# MainBoard_ETH.net
KiCad netlist of a schematic drawn in Altium Designer
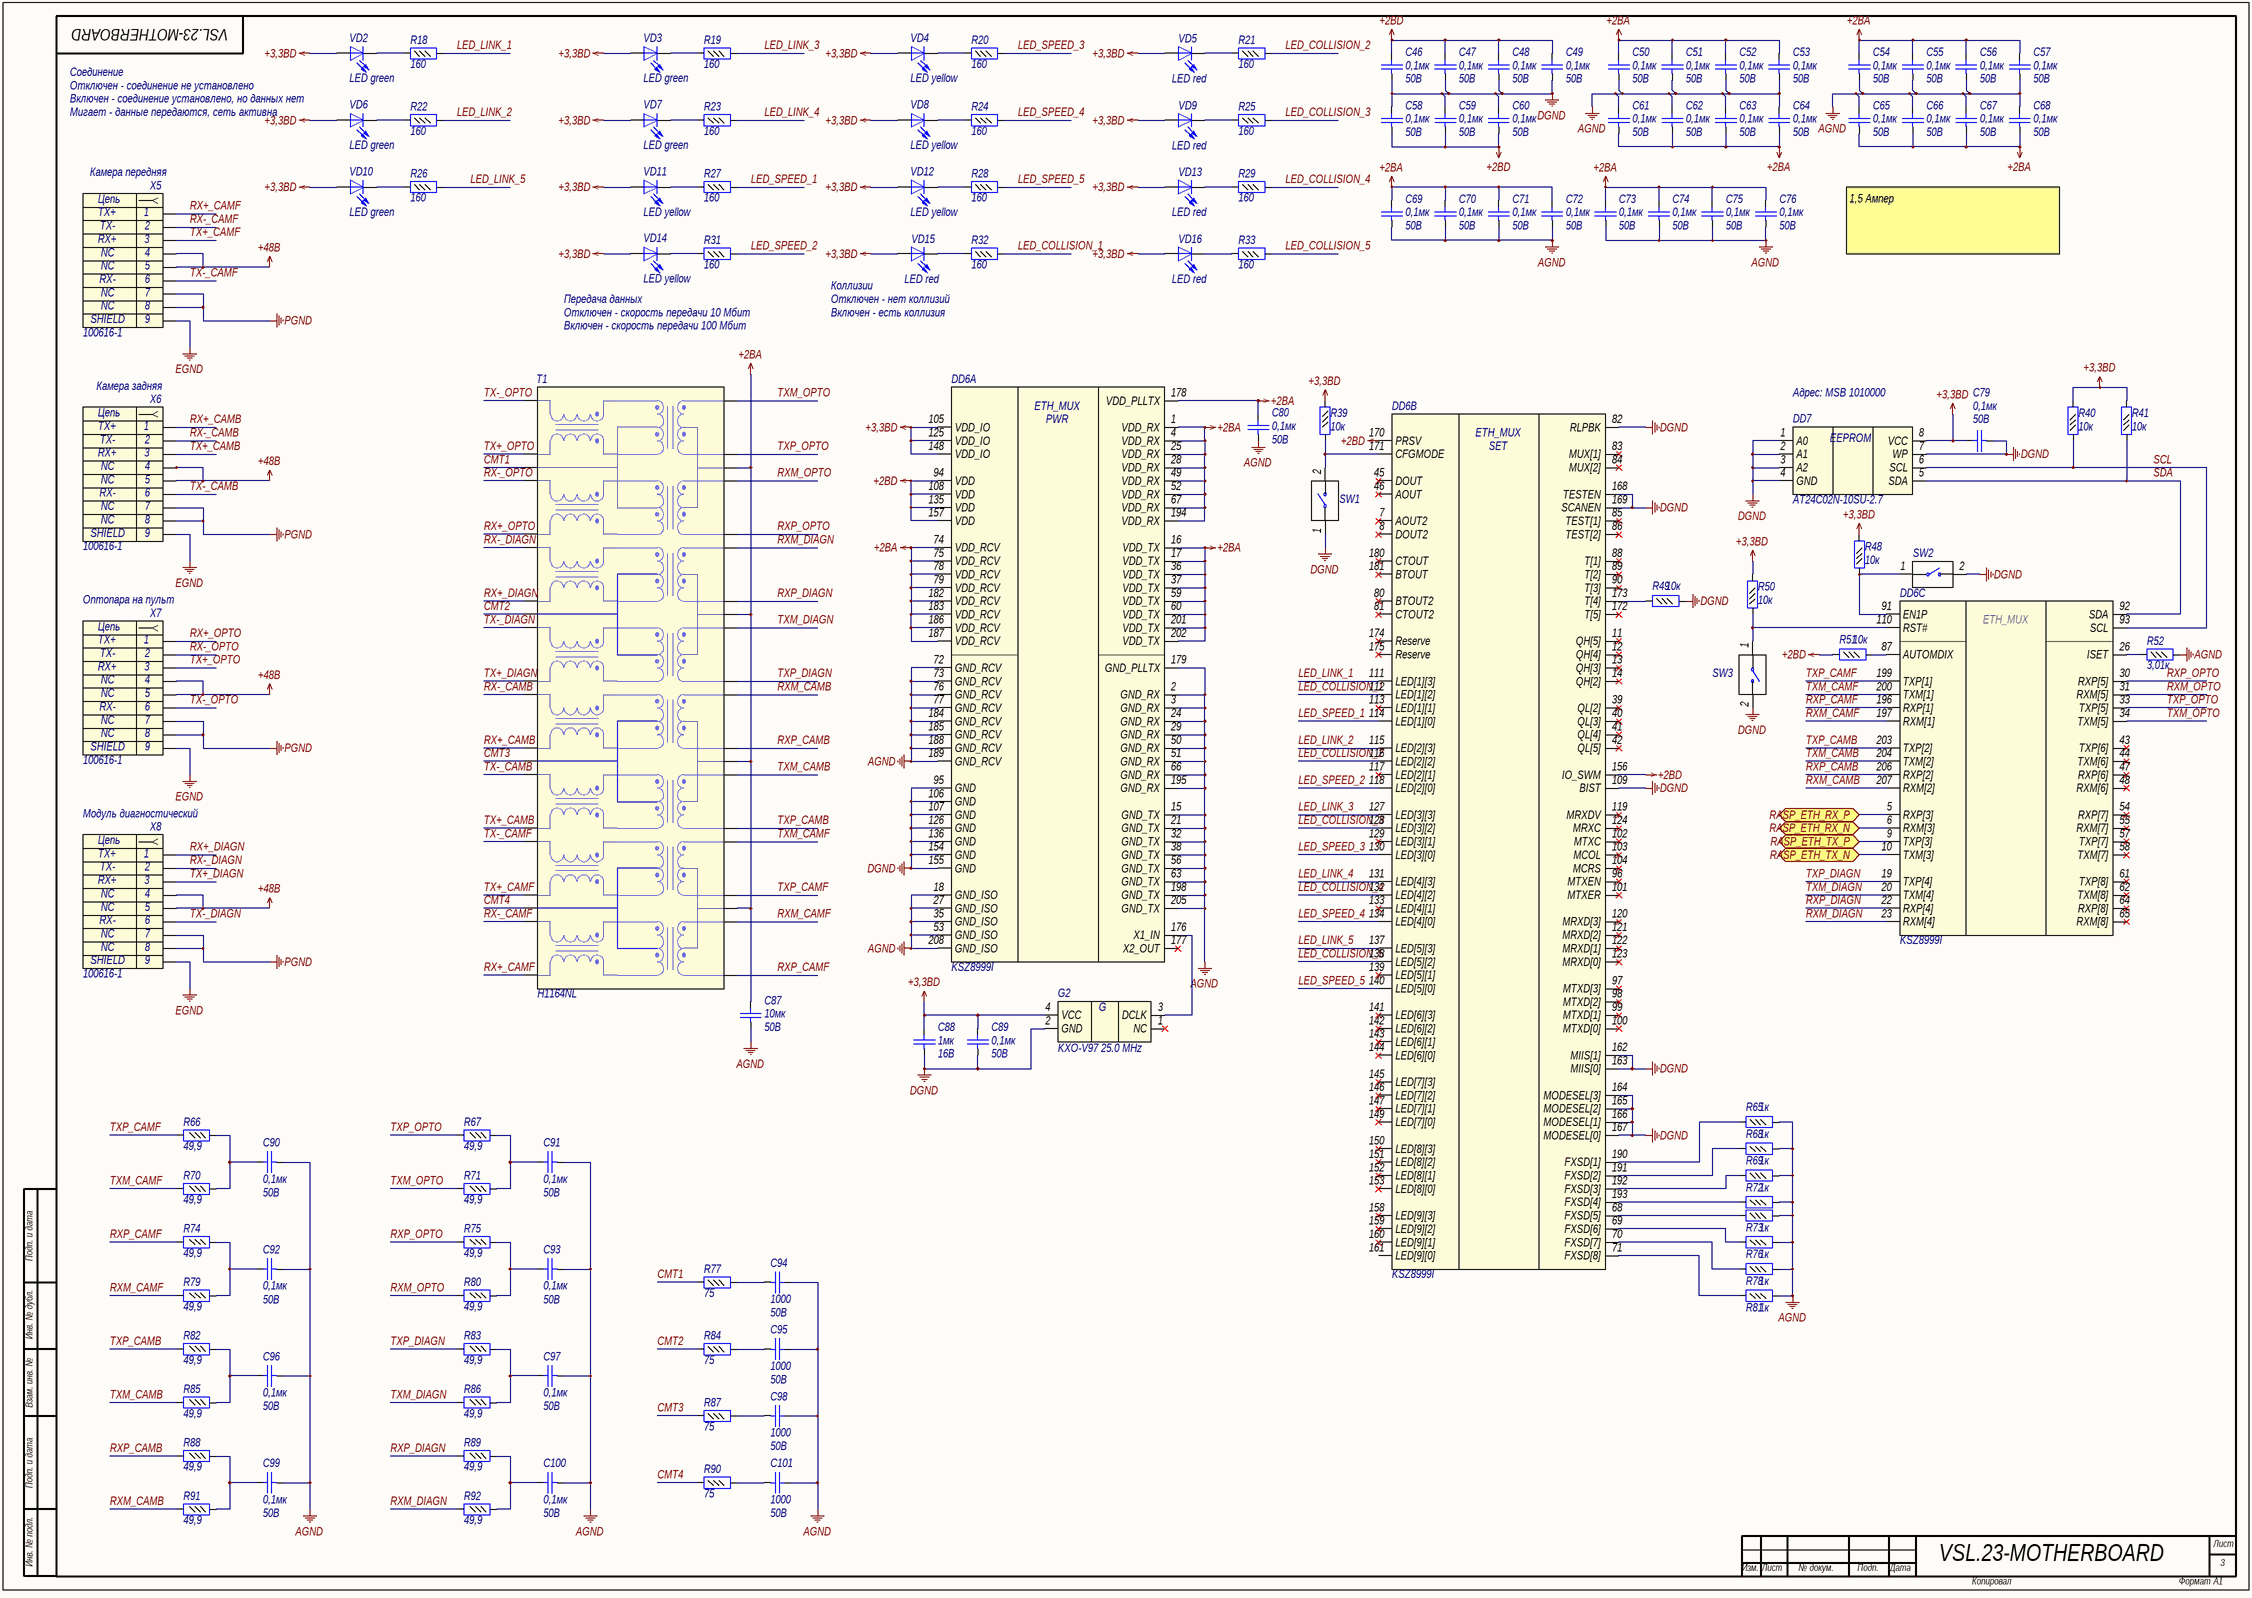
[diagram p0: MainBoard_ETH.SchDoc]

(export (version "E")
  (design (tool "Eeschema 10.0.6"))
  (components
    (comp (ref "C46")
      (value "0,1мк")
      (footprint "C0402")
      (description "Конденсатор")
      (fields
        (field (name "VOLTAGE") "50В")
        (field (name "PART NUMBER") "GRM155R71H104KE14D ")
        (field (name "Comment") "Capacitor")
      )
      (libsource (lib "MOP44") (part "Capacitor"))
    )
    (comp (ref "C47")
      (value "0,1мк")
      (footprint "C0402")
      (description "Конденсатор")
      (fields
        (field (name "VOLTAGE") "50В")
        (field (name "PART NUMBER") "GRM155R71H104KE14D ")
        (field (name "Comment") "Capacitor")
      )
      (libsource (lib "MOP44") (part "Capacitor"))
    )
    (comp (ref "C48")
      (value "0,1мк")
      (footprint "C0402")
      (description "Конденсатор")
      (fields
        (field (name "VOLTAGE") "50В")
        (field (name "PART NUMBER") "GRM155R71H104KE14D ")
        (field (name "Comment") "Capacitor")
      )
      (libsource (lib "MOP44") (part "Capacitor"))
    )
    (comp (ref "C49")
      (value "0,1мк")
      (footprint "C0402")
      (description "Конденсатор")
      (fields
        (field (name "VOLTAGE") "50В")
        (field (name "PART NUMBER") "GRM155R71H104KE14D ")
        (field (name "Comment") "Capacitor")
      )
      (libsource (lib "MOP44") (part "Capacitor"))
    )
    (comp (ref "C50")
      (value "0,1мк")
      (footprint "C0402")
      (description "Конденсатор")
      (fields
        (field (name "VOLTAGE") "50В")
        (field (name "PART NUMBER") "GRM155R71H104KE14D ")
        (field (name "Comment") "Capacitor")
      )
      (libsource (lib "MOP44") (part "Capacitor"))
    )
    (comp (ref "C51")
      (value "0,1мк")
      (footprint "C0402")
      (description "Конденсатор")
      (fields
        (field (name "VOLTAGE") "50В")
        (field (name "PART NUMBER") "GRM155R71H104KE14D ")
        (field (name "Comment") "Capacitor")
      )
      (libsource (lib "MOP44") (part "Capacitor"))
    )
    (comp (ref "C52")
      (value "0,1мк")
      (footprint "C0402")
      (description "Конденсатор")
      (fields
        (field (name "VOLTAGE") "50В")
        (field (name "PART NUMBER") "GRM155R71H104KE14D ")
        (field (name "Comment") "Capacitor")
      )
      (libsource (lib "MOP44") (part "Capacitor"))
    )
    (comp (ref "C53")
      (value "0,1мк")
      (footprint "C0402")
      (description "Конденсатор")
      (fields
        (field (name "VOLTAGE") "50В")
        (field (name "PART NUMBER") "GRM155R71H104KE14D ")
        (field (name "Comment") "Capacitor")
      )
      (libsource (lib "MOP44") (part "Capacitor"))
    )
    (comp (ref "C54")
      (value "0,1мк")
      (footprint "C0402")
      (description "Конденсатор")
      (fields
        (field (name "VOLTAGE") "50В")
        (field (name "PART NUMBER") "GRM155R71H104KE14D ")
        (field (name "Comment") "Capacitor")
      )
      (libsource (lib "MOP44") (part "Capacitor"))
    )
    (comp (ref "C55")
      (value "0,1мк")
      (footprint "C0402")
      (description "Конденсатор")
      (fields
        (field (name "VOLTAGE") "50В")
        (field (name "PART NUMBER") "GRM155R71H104KE14D ")
        (field (name "Comment") "Capacitor")
      )
      (libsource (lib "MOP44") (part "Capacitor"))
    )
    (comp (ref "C56")
      (value "0,1мк")
      (footprint "C0402")
      (description "Конденсатор")
      (fields
        (field (name "VOLTAGE") "50В")
        (field (name "PART NUMBER") "GRM155R71H104KE14D ")
        (field (name "Comment") "Capacitor")
      )
      (libsource (lib "MOP44") (part "Capacitor"))
    )
    (comp (ref "C57")
      (value "0,1мк")
      (footprint "C0402")
      (description "Конденсатор")
      (fields
        (field (name "VOLTAGE") "50В")
        (field (name "PART NUMBER") "GRM155R71H104KE14D ")
        (field (name "Comment") "Capacitor")
      )
      (libsource (lib "MOP44") (part "Capacitor"))
    )
    (comp (ref "C58")
      (value "0,1мк")
      (footprint "C0402")
      (description "Конденсатор")
      (fields
        (field (name "VOLTAGE") "50В")
        (field (name "PART NUMBER") "GRM155R71H104KE14D ")
        (field (name "Comment") "Capacitor")
      )
      (libsource (lib "MOP44") (part "Capacitor"))
    )
    (comp (ref "C59")
      (value "0,1мк")
      (footprint "C0402")
      (description "Конденсатор")
      (fields
        (field (name "VOLTAGE") "50В")
        (field (name "PART NUMBER") "GRM155R71H104KE14D ")
        (field (name "Comment") "Capacitor")
      )
      (libsource (lib "MOP44") (part "Capacitor"))
    )
    (comp (ref "C60")
      (value "0,1мк")
      (footprint "C0402")
      (description "Конденсатор")
      (fields
        (field (name "VOLTAGE") "50В")
        (field (name "PART NUMBER") "GRM155R71H104KE14D ")
        (field (name "Comment") "Capacitor")
      )
      (libsource (lib "MOP44") (part "Capacitor"))
    )
    (comp (ref "C61")
      (value "0,1мк")
      (footprint "C0402")
      (description "Конденсатор")
      (fields
        (field (name "VOLTAGE") "50В")
        (field (name "PART NUMBER") "GRM155R71H104KE14D ")
        (field (name "Comment") "Capacitor")
      )
      (libsource (lib "MOP44") (part "Capacitor"))
    )
    (comp (ref "C62")
      (value "0,1мк")
      (footprint "C0402")
      (description "Конденсатор")
      (fields
        (field (name "VOLTAGE") "50В")
        (field (name "PART NUMBER") "GRM155R71H104KE14D ")
        (field (name "Comment") "Capacitor")
      )
      (libsource (lib "MOP44") (part "Capacitor"))
    )
    (comp (ref "C63")
      (value "0,1мк")
      (footprint "C0402")
      (description "Конденсатор")
      (fields
        (field (name "VOLTAGE") "50В")
        (field (name "PART NUMBER") "GRM155R71H104KE14D ")
        (field (name "Comment") "Capacitor")
      )
      (libsource (lib "MOP44") (part "Capacitor"))
    )
    (comp (ref "C64")
      (value "0,1мк")
      (footprint "C0402")
      (description "Конденсатор")
      (fields
        (field (name "VOLTAGE") "50В")
        (field (name "PART NUMBER") "GRM155R71H104KE14D ")
        (field (name "Comment") "Capacitor")
      )
      (libsource (lib "MOP44") (part "Capacitor"))
    )
    (comp (ref "C65")
      (value "0,1мк")
      (footprint "C0402")
      (description "Конденсатор")
      (fields
        (field (name "VOLTAGE") "50В")
        (field (name "PART NUMBER") "GRM155R71H104KE14D ")
        (field (name "Comment") "Capacitor")
      )
      (libsource (lib "MOP44") (part "Capacitor"))
    )
    (comp (ref "C66")
      (value "0,1мк")
      (footprint "C0402")
      (description "Конденсатор")
      (fields
        (field (name "VOLTAGE") "50В")
        (field (name "PART NUMBER") "GRM155R71H104KE14D ")
        (field (name "Comment") "Capacitor")
      )
      (libsource (lib "MOP44") (part "Capacitor"))
    )
    (comp (ref "C67")
      (value "0,1мк")
      (footprint "C0402")
      (description "Конденсатор")
      (fields
        (field (name "VOLTAGE") "50В")
        (field (name "PART NUMBER") "GRM155R71H104KE14D ")
        (field (name "Comment") "Capacitor")
      )
      (libsource (lib "MOP44") (part "Capacitor"))
    )
    (comp (ref "C68")
      (value "0,1мк")
      (footprint "C0402")
      (description "Конденсатор")
      (fields
        (field (name "VOLTAGE") "50В")
        (field (name "PART NUMBER") "GRM155R71H104KE14D ")
        (field (name "Comment") "Capacitor")
      )
      (libsource (lib "MOP44") (part "Capacitor"))
    )
    (comp (ref "C69")
      (value "0,1мк")
      (footprint "C0402")
      (description "Конденсатор")
      (fields
        (field (name "VOLTAGE") "50В")
        (field (name "PART NUMBER") "GRM155R71H104KE14D ")
        (field (name "Comment") "Capacitor")
      )
      (libsource (lib "MOP44") (part "Capacitor"))
    )
    (comp (ref "C70")
      (value "0,1мк")
      (footprint "C0402")
      (description "Конденсатор")
      (fields
        (field (name "VOLTAGE") "50В")
        (field (name "PART NUMBER") "GRM155R71H104KE14D ")
        (field (name "Comment") "Capacitor")
      )
      (libsource (lib "MOP44") (part "Capacitor"))
    )
    (comp (ref "C71")
      (value "0,1мк")
      (footprint "C0402")
      (description "Конденсатор")
      (fields
        (field (name "VOLTAGE") "50В")
        (field (name "PART NUMBER") "GRM155R71H104KE14D ")
        (field (name "Comment") "Capacitor")
      )
      (libsource (lib "MOP44") (part "Capacitor"))
    )
    (comp (ref "C72")
      (value "0,1мк")
      (footprint "C0402")
      (description "Конденсатор")
      (fields
        (field (name "VOLTAGE") "50В")
        (field (name "PART NUMBER") "GRM155R71H104KE14D ")
        (field (name "Comment") "Capacitor")
      )
      (libsource (lib "MOP44") (part "Capacitor"))
    )
    (comp (ref "C73")
      (value "0,1мк")
      (footprint "C0402")
      (description "Конденсатор")
      (fields
        (field (name "VOLTAGE") "50В")
        (field (name "PART NUMBER") "GRM155R71H104KE14D ")
        (field (name "Comment") "Capacitor")
      )
      (libsource (lib "MOP44") (part "Capacitor"))
    )
    (comp (ref "C74")
      (value "0,1мк")
      (footprint "C0402")
      (description "Конденсатор")
      (fields
        (field (name "VOLTAGE") "50В")
        (field (name "PART NUMBER") "GRM155R71H104KE14D ")
        (field (name "Comment") "Capacitor")
      )
      (libsource (lib "MOP44") (part "Capacitor"))
    )
    (comp (ref "C75")
      (value "0,1мк")
      (footprint "C0402")
      (description "Конденсатор")
      (fields
        (field (name "VOLTAGE") "50В")
        (field (name "PART NUMBER") "GRM155R71H104KE14D ")
        (field (name "Comment") "Capacitor")
      )
      (libsource (lib "MOP44") (part "Capacitor"))
    )
    (comp (ref "C76")
      (value "0,1мк")
      (footprint "C0402")
      (description "Конденсатор")
      (fields
        (field (name "VOLTAGE") "50В")
        (field (name "PART NUMBER") "GRM155R71H104KE14D ")
        (field (name "Comment") "Capacitor")
      )
      (libsource (lib "MOP44") (part "Capacitor"))
    )
    (comp (ref "C79")
      (value "0,1мк")
      (footprint "C0402")
      (description "Конденсатор")
      (fields
        (field (name "VOLTAGE") "50В")
        (field (name "PART NUMBER") "GRM155R71H104KE14D ")
        (field (name "Comment") "Capacitor")
      )
      (libsource (lib "MOP44") (part "Capacitor"))
    )
    (comp (ref "C80")
      (value "0,1мк")
      (footprint "C0402")
      (description "Конденсатор")
      (fields
        (field (name "VOLTAGE") "50В")
        (field (name "PART NUMBER") "GRM155R71H104KE14D ")
        (field (name "Comment") "Capacitor")
      )
      (libsource (lib "MOP44") (part "Capacitor"))
    )
    (comp (ref "C87")
      (value "10мк")
      (footprint "C1210")
      (description "Конденсатор")
      (fields (field (name "VOLTAGE") "50В") (field (name "PART NUMBER") "C3225X7R1H106K250AC"))
      (libsource (lib "MOP44") (part "Capacitor"))
    )
    (comp (ref "C88")
      (value "1мк")
      (footprint "C0603")
      (description "Конденсатор")
      (fields
        (field (name "VOLTAGE") "16B")
        (field (name "PART NUMBER") "GRM188R71C105KA12D**")
        (field (name "Comment") "Capacitor")
      )
      (libsource (lib "MOP44") (part "Capacitor"))
    )
    (comp (ref "C89")
      (value "0,1мк")
      (footprint "C0402")
      (description "Конденсатор")
      (fields
        (field (name "VOLTAGE") "50В")
        (field (name "PART NUMBER") "GRM155R71H104KE14D ")
        (field (name "Comment") "Capacitor")
      )
      (libsource (lib "MOP44") (part "Capacitor"))
    )
    (comp (ref "C90")
      (value "0,1мк")
      (footprint "C0402")
      (description "Конденсатор")
      (fields
        (field (name "VOLTAGE") "50В")
        (field (name "PART NUMBER") "GRM155R71H104KE14D ")
        (field (name "Comment") "Capacitor")
      )
      (libsource (lib "MOP44") (part "Capacitor"))
    )
    (comp (ref "C91")
      (value "0,1мк")
      (footprint "C0402")
      (description "Конденсатор")
      (fields
        (field (name "VOLTAGE") "50В")
        (field (name "PART NUMBER") "GRM155R71H104KE14D ")
        (field (name "Comment") "Capacitor")
      )
      (libsource (lib "MOP44") (part "Capacitor"))
    )
    (comp (ref "C92")
      (value "0,1мк")
      (footprint "C0402")
      (description "Конденсатор")
      (fields
        (field (name "VOLTAGE") "50В")
        (field (name "PART NUMBER") "GRM155R71H104KE14D ")
        (field (name "Comment") "Capacitor")
      )
      (libsource (lib "MOP44") (part "Capacitor"))
    )
    (comp (ref "C93")
      (value "0,1мк")
      (footprint "C0402")
      (description "Конденсатор")
      (fields
        (field (name "VOLTAGE") "50В")
        (field (name "PART NUMBER") "GRM155R71H104KE14D ")
        (field (name "Comment") "Capacitor")
      )
      (libsource (lib "MOP44") (part "Capacitor"))
    )
    (comp (ref "C94")
      (value "1000")
      (footprint "C0402")
      (description "Конденсатор")
      (fields (field (name "VOLTAGE") "50B") (field (name "PART NUMBER") "GRM155R71H102K*"))
      (libsource (lib "MOP44") (part "Capacitor"))
    )
    (comp (ref "C95")
      (value "1000")
      (footprint "C0402")
      (description "Конденсатор")
      (fields (field (name "VOLTAGE") "50B") (field (name "PART NUMBER") "GRM155R71H102K*"))
      (libsource (lib "MOP44") (part "Capacitor"))
    )
    (comp (ref "C96")
      (value "0,1мк")
      (footprint "C0402")
      (description "Конденсатор")
      (fields
        (field (name "VOLTAGE") "50В")
        (field (name "PART NUMBER") "GRM155R71H104KE14D ")
        (field (name "Comment") "Capacitor")
      )
      (libsource (lib "MOP44") (part "Capacitor"))
    )
    (comp (ref "C97")
      (value "0,1мк")
      (footprint "C0402")
      (description "Конденсатор")
      (fields
        (field (name "VOLTAGE") "50В")
        (field (name "PART NUMBER") "GRM155R71H104KE14D ")
        (field (name "Comment") "Capacitor")
      )
      (libsource (lib "MOP44") (part "Capacitor"))
    )
    (comp (ref "C98")
      (value "1000")
      (footprint "C0402")
      (description "Конденсатор")
      (fields (field (name "VOLTAGE") "50B") (field (name "PART NUMBER") "GRM155R71H102K*"))
      (libsource (lib "MOP44") (part "Capacitor"))
    )
    (comp (ref "C99")
      (value "0,1мк")
      (footprint "C0402")
      (description "Конденсатор")
      (fields
        (field (name "VOLTAGE") "50В")
        (field (name "PART NUMBER") "GRM155R71H104KE14D ")
        (field (name "Comment") "Capacitor")
      )
      (libsource (lib "MOP44") (part "Capacitor"))
    )
    (comp (ref "C100")
      (value "0,1мк")
      (footprint "C0402")
      (description "Конденсатор")
      (fields
        (field (name "VOLTAGE") "50В")
        (field (name "PART NUMBER") "GRM155R71H104KE14D ")
        (field (name "Comment") "Capacitor")
      )
      (libsource (lib "MOP44") (part "Capacitor"))
    )
    (comp (ref "C101")
      (value "1000")
      (footprint "C0402")
      (description "Конденсатор")
      (fields (field (name "VOLTAGE") "50B") (field (name "PART NUMBER") "GRM155R71H102K*"))
      (libsource (lib "MOP44") (part "Capacitor"))
    )
    (comp (ref "DD6")
      (value "~")
      (footprint "PQFP208")
      (description "9-Port 10/100 Unmanaged Ethernet Switch")
      (fields (field (name "PART NUMBER") "KSZ8999I"))
      (libsource (lib "MOP44") (part "KSZ8999"))
    )
    (comp (ref "DD7")
      (value "AT24C0x")
      (footprint "SO8")
      (description "Two-wire  Serial EEPROM")
      (fields (field (name "MANUFACTURER") "Microchip") (field (name "PART NUMBER") "AT24C02N-10SU-2.7"))
      (libsource (lib "MOP44") (part "AT24C0x"))
    )
    (comp (ref "G2")
      (value "KXO")
      (footprint "QSMD7x5.2x1.8")
      (description "Кварц. генер. 32.768 МГц (HCMOS/TTL)")
      (fields (field (name "PART NUMBER") "KXO-V97 25.0 MHz"))
      (libsource (lib "MOP44") (part "KXO"))
    )
    (comp (ref "R18")
      (value "160")
      (footprint "R0402")
      (description "Резистор")
      (fields (field (name "PART NUMBER") "RC0402FR-07160RL") (field (name "POWER") "0,062Вт"))
      (libsource (lib "") (part "Resistor_0,062Вт_1"))
    )
    (comp (ref "R19")
      (value "160")
      (footprint "R0402")
      (description "Резистор")
      (fields (field (name "PART NUMBER") "RC0402FR-07160RL") (field (name "POWER") "0,062Вт"))
      (libsource (lib "") (part "Resistor_0,062Вт_1"))
    )
    (comp (ref "R20")
      (value "160")
      (footprint "R0402")
      (description "Резистор")
      (fields (field (name "PART NUMBER") "RC0402FR-07160RL") (field (name "POWER") "0,062Вт"))
      (libsource (lib "") (part "Resistor_0,062Вт_1"))
    )
    (comp (ref "R21")
      (value "160")
      (footprint "R0402")
      (description "Резистор")
      (fields (field (name "PART NUMBER") "RC0402FR-07160RL") (field (name "POWER") "0,062Вт"))
      (libsource (lib "") (part "Resistor_0,062Вт_1"))
    )
    (comp (ref "R22")
      (value "160")
      (footprint "R0402")
      (description "Резистор")
      (fields (field (name "PART NUMBER") "RC0402FR-07160RL") (field (name "POWER") "0,062Вт"))
      (libsource (lib "") (part "Resistor_0,062Вт_1"))
    )
    (comp (ref "R23")
      (value "160")
      (footprint "R0402")
      (description "Резистор")
      (fields (field (name "PART NUMBER") "RC0402FR-07160RL") (field (name "POWER") "0,062Вт"))
      (libsource (lib "") (part "Resistor_0,062Вт_1"))
    )
    (comp (ref "R24")
      (value "160")
      (footprint "R0402")
      (description "Резистор")
      (fields (field (name "PART NUMBER") "RC0402FR-07160RL") (field (name "POWER") "0,062Вт"))
      (libsource (lib "") (part "Resistor_0,062Вт_1"))
    )
    (comp (ref "R25")
      (value "160")
      (footprint "R0402")
      (description "Резистор")
      (fields (field (name "PART NUMBER") "RC0402FR-07160RL") (field (name "POWER") "0,062Вт"))
      (libsource (lib "") (part "Resistor_0,062Вт_1"))
    )
    (comp (ref "R26")
      (value "160")
      (footprint "R0402")
      (description "Резистор")
      (fields (field (name "PART NUMBER") "RC0402FR-07160RL") (field (name "POWER") "0,062Вт"))
      (libsource (lib "") (part "Resistor_0,062Вт_1"))
    )
    (comp (ref "R27")
      (value "160")
      (footprint "R0402")
      (description "Резистор")
      (fields (field (name "PART NUMBER") "RC0402FR-07160RL") (field (name "POWER") "0,062Вт"))
      (libsource (lib "") (part "Resistor_0,062Вт_1"))
    )
    (comp (ref "R28")
      (value "160")
      (footprint "R0402")
      (description "Резистор")
      (fields (field (name "PART NUMBER") "RC0402FR-07160RL") (field (name "POWER") "0,062Вт"))
      (libsource (lib "") (part "Resistor_0,062Вт_1"))
    )
    (comp (ref "R29")
      (value "160")
      (footprint "R0402")
      (description "Резистор")
      (fields (field (name "PART NUMBER") "RC0402FR-07160RL") (field (name "POWER") "0,062Вт"))
      (libsource (lib "") (part "Resistor_0,062Вт_1"))
    )
    (comp (ref "R31")
      (value "160")
      (footprint "R0402")
      (description "Резистор")
      (fields (field (name "PART NUMBER") "RC0402FR-07160RL") (field (name "POWER") "0,062Вт"))
      (libsource (lib "") (part "Resistor_0,062Вт_1"))
    )
    (comp (ref "R32")
      (value "160")
      (footprint "R0402")
      (description "Резистор")
      (fields (field (name "PART NUMBER") "RC0402FR-07160RL") (field (name "POWER") "0,062Вт"))
      (libsource (lib "") (part "Resistor_0,062Вт_1"))
    )
    (comp (ref "R33")
      (value "160")
      (footprint "R0402")
      (description "Резистор")
      (fields (field (name "PART NUMBER") "RC0402FR-07160RL") (field (name "POWER") "0,062Вт"))
      (libsource (lib "") (part "Resistor_0,062Вт_1"))
    )
    (comp (ref "R39")
      (value "10к")
      (footprint "R0402")
      (description "Резистор")
      (fields (field (name "PART NUMBER") "RC0402FR-0710KL") (field (name "POWER") "0,062Вт"))
      (libsource (lib "") (part "Resistor_0,062Вт_3"))
    )
    (comp (ref "R40")
      (value "10к")
      (footprint "R0402")
      (description "Резистор")
      (fields (field (name "PART NUMBER") "RC0402FR-0710KL") (field (name "POWER") "0,062Вт"))
      (libsource (lib "") (part "Resistor_0,062Вт_2"))
    )
    (comp (ref "R41")
      (value "10к")
      (footprint "R0402")
      (description "Резистор")
      (fields (field (name "PART NUMBER") "RC0402FR-0710KL") (field (name "POWER") "0,062Вт"))
      (libsource (lib "") (part "Resistor_0,062Вт_2"))
    )
    (comp (ref "R48")
      (value "10к")
      (footprint "R0402")
      (description "Резистор")
      (fields (field (name "PART NUMBER") "RC0402FR-0710KL") (field (name "POWER") "0,062Вт"))
      (libsource (lib "") (part "Resistor_0,062Вт_2"))
    )
    (comp (ref "R49")
      (value "10к")
      (footprint "R0402")
      (description "Резистор")
      (fields (field (name "PART NUMBER") "RC0402FR-0710KL") (field (name "POWER") "0,062Вт"))
      (libsource (lib "") (part "Resistor_0,062Вт_1"))
    )
    (comp (ref "R50")
      (value "10к")
      (footprint "R0402")
      (description "Резистор")
      (fields (field (name "PART NUMBER") "RC0402FR-0710KL") (field (name "POWER") "0,062Вт"))
      (libsource (lib "") (part "Resistor_0,062Вт_2"))
    )
    (comp (ref "R51")
      (value "10к")
      (footprint "R0402")
      (description "Резистор")
      (fields (field (name "PART NUMBER") "RC0402FR-0710KL") (field (name "POWER") "0,062Вт"))
      (libsource (lib "") (part "Resistor_0,062Вт_1"))
    )
    (comp (ref "R52")
      (value "3,01к")
      (footprint "R0402")
      (description "Резистор")
      (fields (field (name "PART NUMBER") "RC0402FR-073K01L") (field (name "POWER") "0,062Вт"))
      (libsource (lib "") (part "Resistor_0,062Вт_1"))
    )
    (comp (ref "R65")
      (value "1к")
      (footprint "R0402")
      (description "Резистор")
      (fields (field (name "PART NUMBER") "RC0402FR-071KL") (field (name "POWER") "0,062Вт"))
      (libsource (lib "") (part "Resistor_0,062Вт_1"))
    )
    (comp (ref "R66")
      (value "49,9")
      (footprint "R0402")
      (description "Резистор")
      (fields (field (name "PART NUMBER") "RC0402FR-0749R9L") (field (name "POWER") "0,062Вт"))
      (libsource (lib "MOP44") (part "Resistor_0,062Вт"))
    )
    (comp (ref "R67")
      (value "49,9")
      (footprint "R0402")
      (description "Резистор")
      (fields (field (name "PART NUMBER") "RC0402FR-0749R9L") (field (name "POWER") "0,062Вт"))
      (libsource (lib "MOP44") (part "Resistor_0,062Вт"))
    )
    (comp (ref "R68")
      (value "1к")
      (footprint "R0402")
      (description "Резистор")
      (fields (field (name "PART NUMBER") "RC0402FR-071KL") (field (name "POWER") "0,062Вт"))
      (libsource (lib "") (part "Resistor_0,062Вт_1"))
    )
    (comp (ref "R69")
      (value "1к")
      (footprint "R0402")
      (description "Резистор")
      (fields (field (name "PART NUMBER") "RC0402FR-071KL") (field (name "POWER") "0,062Вт"))
      (libsource (lib "") (part "Resistor_0,062Вт_1"))
    )
    (comp (ref "R70")
      (value "49,9")
      (footprint "R0402")
      (description "Резистор")
      (fields (field (name "PART NUMBER") "RC0402FR-0749R9L") (field (name "POWER") "0,062Вт"))
      (libsource (lib "MOP44") (part "Resistor_0,062Вт"))
    )
    (comp (ref "R71")
      (value "49,9")
      (footprint "R0402")
      (description "Резистор")
      (fields (field (name "PART NUMBER") "RC0402FR-0749R9L") (field (name "POWER") "0,062Вт"))
      (libsource (lib "MOP44") (part "Resistor_0,062Вт"))
    )
    (comp (ref "R72")
      (value "1к")
      (footprint "R0402")
      (description "Резистор")
      (fields (field (name "PART NUMBER") "RC0402FR-071KL") (field (name "POWER") "0,062Вт"))
      (libsource (lib "") (part "Resistor_0,062Вт_1"))
    )
    (comp (ref "R73")
      (value "1к")
      (footprint "R0402")
      (description "Резистор")
      (fields (field (name "PART NUMBER") "RC0402FR-071KL") (field (name "POWER") "0,062Вт"))
      (libsource (lib "") (part "Resistor_0,062Вт_1"))
    )
    (comp (ref "R74")
      (value "49,9")
      (footprint "R0402")
      (description "Резистор")
      (fields (field (name "PART NUMBER") "RC0402FR-0749R9L") (field (name "POWER") "0,062Вт"))
      (libsource (lib "MOP44") (part "Resistor_0,062Вт"))
    )
    (comp (ref "R75")
      (value "49,9")
      (footprint "R0402")
      (description "Резистор")
      (fields (field (name "PART NUMBER") "RC0402FR-0749R9L") (field (name "POWER") "0,062Вт"))
      (libsource (lib "MOP44") (part "Resistor_0,062Вт"))
    )
    (comp (ref "R76")
      (value "1к")
      (footprint "R0402")
      (description "Резистор")
      (fields (field (name "PART NUMBER") "RC0402FR-071KL") (field (name "POWER") "0,062Вт"))
      (libsource (lib "") (part "Resistor_0,062Вт_1"))
    )
    (comp (ref "R77")
      (value "75")
      (footprint "R0402")
      (description "Резистор")
      (fields (field (name "PART NUMBER") "RC0402FR-0775RL") (field (name "POWER") "0,062Вт"))
      (libsource (lib "") (part "Resistor_0,062Вт_1"))
    )
    (comp (ref "R78")
      (value "1к")
      (footprint "R0402")
      (description "Резистор")
      (fields (field (name "PART NUMBER") "RC0402FR-071KL") (field (name "POWER") "0,062Вт"))
      (libsource (lib "") (part "Resistor_0,062Вт_1"))
    )
    (comp (ref "R79")
      (value "49,9")
      (footprint "R0402")
      (description "Резистор")
      (fields (field (name "PART NUMBER") "RC0402FR-0749R9L") (field (name "POWER") "0,062Вт"))
      (libsource (lib "MOP44") (part "Resistor_0,062Вт"))
    )
    (comp (ref "R80")
      (value "49,9")
      (footprint "R0402")
      (description "Резистор")
      (fields (field (name "PART NUMBER") "RC0402FR-0749R9L") (field (name "POWER") "0,062Вт"))
      (libsource (lib "MOP44") (part "Resistor_0,062Вт"))
    )
    (comp (ref "R81")
      (value "1к")
      (footprint "R0402")
      (description "Резистор")
      (fields (field (name "PART NUMBER") "RC0402FR-071KL") (field (name "POWER") "0,062Вт"))
      (libsource (lib "") (part "Resistor_0,062Вт_1"))
    )
    (comp (ref "R82")
      (value "49,9")
      (footprint "R0402")
      (description "Резистор")
      (fields (field (name "PART NUMBER") "RC0402FR-0749R9L") (field (name "POWER") "0,062Вт"))
      (libsource (lib "MOP44") (part "Resistor_0,062Вт"))
    )
    (comp (ref "R83")
      (value "49,9")
      (footprint "R0402")
      (description "Резистор")
      (fields (field (name "PART NUMBER") "RC0402FR-0749R9L") (field (name "POWER") "0,062Вт"))
      (libsource (lib "MOP44") (part "Resistor_0,062Вт"))
    )
    (comp (ref "R84")
      (value "75")
      (footprint "R0402")
      (description "Резистор")
      (fields (field (name "PART NUMBER") "RC0402FR-0775RL") (field (name "POWER") "0,062Вт"))
      (libsource (lib "") (part "Resistor_0,062Вт_1"))
    )
    (comp (ref "R85")
      (value "49,9")
      (footprint "R0402")
      (description "Резистор")
      (fields (field (name "PART NUMBER") "RC0402FR-0749R9L") (field (name "POWER") "0,062Вт"))
      (libsource (lib "MOP44") (part "Resistor_0,062Вт"))
    )
    (comp (ref "R86")
      (value "49,9")
      (footprint "R0402")
      (description "Резистор")
      (fields (field (name "PART NUMBER") "RC0402FR-0749R9L") (field (name "POWER") "0,062Вт"))
      (libsource (lib "MOP44") (part "Resistor_0,062Вт"))
    )
    (comp (ref "R87")
      (value "75")
      (footprint "R0402")
      (description "Резистор")
      (fields (field (name "PART NUMBER") "RC0402FR-0775RL") (field (name "POWER") "0,062Вт"))
      (libsource (lib "") (part "Resistor_0,062Вт_1"))
    )
    (comp (ref "R88")
      (value "49,9")
      (footprint "R0402")
      (description "Резистор")
      (fields (field (name "PART NUMBER") "RC0402FR-0749R9L") (field (name "POWER") "0,062Вт"))
      (libsource (lib "MOP44") (part "Resistor_0,062Вт"))
    )
    (comp (ref "R89")
      (value "49,9")
      (footprint "R0402")
      (description "Резистор")
      (fields (field (name "PART NUMBER") "RC0402FR-0749R9L") (field (name "POWER") "0,062Вт"))
      (libsource (lib "MOP44") (part "Resistor_0,062Вт"))
    )
    (comp (ref "R90")
      (value "75")
      (footprint "R0402")
      (description "Резистор")
      (fields (field (name "PART NUMBER") "RC0402FR-0775RL") (field (name "POWER") "0,062Вт"))
      (libsource (lib "") (part "Resistor_0,062Вт_1"))
    )
    (comp (ref "R91")
      (value "49,9")
      (footprint "R0402")
      (description "Резистор")
      (fields (field (name "PART NUMBER") "RC0402FR-0749R9L") (field (name "POWER") "0,062Вт"))
      (libsource (lib "MOP44") (part "Resistor_0,062Вт"))
    )
    (comp (ref "R92")
      (value "49,9")
      (footprint "R0402")
      (description "Резистор")
      (fields (field (name "PART NUMBER") "RC0402FR-0749R9L") (field (name "POWER") "0,062Вт"))
      (libsource (lib "MOP44") (part "Resistor_0,062Вт"))
    )
    (comp (ref "SW1")
      (value "DS1040-01")
      (footprint "JUMPER_2.54")
      (description "DIP переключатель")
      (libsource (lib "MOP44") (part "DS1040-01"))
    )
    (comp (ref "SW2")
      (value "DS1040-01")
      (footprint "1PAD_ADR")
      (description "DIP переключатель")
      (libsource (lib "MOP44") (part "DS1040-01"))
    )
    (comp (ref "SW3")
      (value "DS1040-01")
      (footprint "JUMPER_2.54")
      (description "DIP переключатель")
      (libsource (lib "MOP44") (part "DS1040-01"))
    )
    (comp (ref "T1")
      (value "ETH Trasformer")
      (footprint "H1164NL_TRANS")
      (description "EMI Suppression Filter")
      (fields (field (name "PART NUMBER") "H1164NL"))
      (libsource (lib "MOP44") (part "ETH Trasformer"))
    )
    (comp (ref "VD2")
      (value "LED")
      (footprint "L_0402_GREEN")
      (description "Светодиод")
      (fields (field (name "PART NAME") "LED green") (field (name "PART NUMBER") "KPHHS-1005MGCK "))
      (libsource (lib "MOP44") (part "LED"))
    )
    (comp (ref "VD3")
      (value "LED")
      (footprint "L_0402_GREEN")
      (description "Светодиод")
      (fields (field (name "PART NAME") "LED green") (field (name "PART NUMBER") "KPHHS-1005MGCK "))
      (libsource (lib "MOP44") (part "LED"))
    )
    (comp (ref "VD4")
      (value "LED")
      (footprint "L_0402_YELLOW")
      (description "Светодиод")
      (fields (field (name "PART NAME") "LED yellow") (field (name "PART NUMBER") "KPHHS-1005SYCK"))
      (libsource (lib "MOP44") (part "LED"))
    )
    (comp (ref "VD5")
      (value "LED")
      (footprint "L_0402_RED")
      (description "Светодиод")
      (fields (field (name "PART NAME") "LED red") (field (name "PART NUMBER") "KPHHS-1005SURCK"))
      (libsource (lib "MOP44") (part "LED"))
    )
    (comp (ref "VD6")
      (value "LED")
      (footprint "L_0402_GREEN")
      (description "Светодиод")
      (fields (field (name "PART NAME") "LED green") (field (name "PART NUMBER") "KPHHS-1005MGCK "))
      (libsource (lib "MOP44") (part "LED"))
    )
    (comp (ref "VD7")
      (value "LED")
      (footprint "L_0402_GREEN")
      (description "Светодиод")
      (fields (field (name "PART NAME") "LED green") (field (name "PART NUMBER") "KPHHS-1005MGCK "))
      (libsource (lib "MOP44") (part "LED"))
    )
    (comp (ref "VD8")
      (value "LED")
      (footprint "L_0402_YELLOW")
      (description "Светодиод")
      (fields (field (name "PART NAME") "LED yellow") (field (name "PART NUMBER") "KPHHS-1005SYCK"))
      (libsource (lib "MOP44") (part "LED"))
    )
    (comp (ref "VD9")
      (value "LED")
      (footprint "L_0402_RED")
      (description "Светодиод")
      (fields (field (name "PART NAME") "LED red") (field (name "PART NUMBER") "KPHHS-1005SURCK"))
      (libsource (lib "MOP44") (part "LED"))
    )
    (comp (ref "VD10")
      (value "LED")
      (footprint "L_0402_GREEN")
      (description "Светодиод")
      (fields (field (name "PART NAME") "LED green") (field (name "PART NUMBER") "KPHHS-1005MGCK "))
      (libsource (lib "MOP44") (part "LED"))
    )
    (comp (ref "VD11")
      (value "LED")
      (footprint "L_0402_YELLOW")
      (description "Светодиод")
      (fields (field (name "PART NAME") "LED yellow") (field (name "PART NUMBER") "KPHHS-1005SYCK"))
      (libsource (lib "MOP44") (part "LED"))
    )
    (comp (ref "VD12")
      (value "LED")
      (footprint "L_0402_YELLOW")
      (description "Светодиод")
      (fields (field (name "PART NAME") "LED yellow") (field (name "PART NUMBER") "KPHHS-1005SYCK"))
      (libsource (lib "MOP44") (part "LED"))
    )
    (comp (ref "VD13")
      (value "LED")
      (footprint "L_0402_RED")
      (description "Светодиод")
      (fields (field (name "PART NAME") "LED red") (field (name "PART NUMBER") "KPHHS-1005SURCK"))
      (libsource (lib "MOP44") (part "LED"))
    )
    (comp (ref "VD14")
      (value "LED")
      (footprint "L_0402_YELLOW")
      (description "Светодиод")
      (fields (field (name "PART NAME") "LED yellow") (field (name "PART NUMBER") "KPHHS-1005SYCK"))
      (libsource (lib "MOP44") (part "LED"))
    )
    (comp (ref "VD15")
      (value "LED")
      (footprint "L_0402_RED")
      (description "Светодиод")
      (fields (field (name "PART NAME") "LED red") (field (name "PART NUMBER") "KPHHS-1005SURCK"))
      (libsource (lib "MOP44") (part "LED"))
    )
    (comp (ref "VD16")
      (value "LED")
      (footprint "L_0402_RED")
      (description "Светодиод")
      (fields (field (name "PART NAME") "LED red") (field (name "PART NUMBER") "KPHHS-1005SURCK"))
      (libsource (lib "MOP44") (part "LED"))
    )
    (comp (ref "X5")
      (value "Камера передняя")
      (footprint "RJ45_100616-1")
      (description "Разъем - 9 конт. розетка")
      (fields (field (name "PART NUMBER") "100616-1"))
      (libsource (lib "MOP44") (part "Header_9_sct"))
    )
    (comp (ref "X6")
      (value "Камера задняя")
      (footprint "RJ45_100616-1")
      (description "Разъем - 9 конт. розетка")
      (fields (field (name "PART NUMBER") "100616-1"))
      (libsource (lib "MOP44") (part "Header_9_sct"))
    )
    (comp (ref "X7")
      (value "Оптопара на пульт")
      (footprint "RJ45_100616-1")
      (description "Разъем - 9 конт. розетка")
      (fields (field (name "PART NUMBER") "100616-1"))
      (libsource (lib "MOP44") (part "Header_9_sct"))
    )
    (comp (ref "X8")
      (value "Модуль диагностический")
      (footprint "RJ45_100616-1")
      (description "Разъем - 9 конт. розетка")
      (fields (field (name "PART NUMBER") "100616-1"))
      (libsource (lib "MOP44") (part "Header_9_sct"))
    )
  )
  (nets
    (net (code "1") (name "+2BA") (class "Default")
      (node (ref "C50") (pin "2") (pinfunction "2_2") (pintype "passive"))
      (node (ref "C51") (pin "2") (pinfunction "2_2") (pintype "passive"))
      (node (ref "C52") (pin "2") (pinfunction "2_2") (pintype "passive"))
      (node (ref "C53") (pin "2") (pinfunction "2_2") (pintype "passive"))
      (node (ref "C54") (pin "2") (pinfunction "2_2") (pintype "passive"))
      (node (ref "C55") (pin "2") (pinfunction "2_2") (pintype "passive"))
      (node (ref "C56") (pin "2") (pinfunction "2_2") (pintype "passive"))
      (node (ref "C57") (pin "2") (pinfunction "2_2") (pintype "passive"))
      (node (ref "C61") (pin "1") (pinfunction "1_1") (pintype "passive"))
      (node (ref "C62") (pin "1") (pinfunction "1_1") (pintype "passive"))
      (node (ref "C63") (pin "1") (pinfunction "1_1") (pintype "passive"))
      (node (ref "C64") (pin "1") (pinfunction "1_1") (pintype "passive"))
      (node (ref "C65") (pin "1") (pinfunction "1_1") (pintype "passive"))
      (node (ref "C66") (pin "1") (pinfunction "1_1") (pintype "passive"))
      (node (ref "C67") (pin "1") (pinfunction "1_1") (pintype "passive"))
      (node (ref "C68") (pin "1") (pinfunction "1_1") (pintype "passive"))
      (node (ref "C69") (pin "2") (pinfunction "2_2") (pintype "passive"))
      (node (ref "C70") (pin "2") (pinfunction "2_2") (pintype "passive"))
      (node (ref "C71") (pin "2") (pinfunction "2_2") (pintype "passive"))
      (node (ref "C72") (pin "2") (pinfunction "2_2") (pintype "passive"))
      (node (ref "C73") (pin "2") (pinfunction "2_2") (pintype "passive"))
      (node (ref "C74") (pin "2") (pinfunction "2_2") (pintype "passive"))
      (node (ref "C75") (pin "2") (pinfunction "2_2") (pintype "passive"))
      (node (ref "C76") (pin "2") (pinfunction "2_2") (pintype "passive"))
      (node (ref "C80") (pin "2") (pinfunction "2_2") (pintype "passive"))
      (node (ref "C87") (pin "2") (pinfunction "2_2") (pintype "passive"))
      (node (ref "DD6") (pin "1") (pinfunction "VDD_RX_1") (pintype "power_in"))
      (node (ref "DD6") (pin "16") (pinfunction "VDD_TX_16") (pintype "power_in"))
      (node (ref "DD6") (pin "17") (pinfunction "VDD_TX_17") (pintype "power_in"))
      (node (ref "DD6") (pin "178") (pinfunction "VDD_PLLTX_178") (pintype "power_in"))
      (node (ref "DD6") (pin "182") (pinfunction "VDD_RCV_182") (pintype "power_in"))
      (node (ref "DD6") (pin "183") (pinfunction "VDD_RCV_183") (pintype "power_in"))
      (node (ref "DD6") (pin "186") (pinfunction "VDD_RCV_186") (pintype "power_in"))
      (node (ref "DD6") (pin "187") (pinfunction "VDD_RCV_187") (pintype "power_in"))
      (node (ref "DD6") (pin "194") (pinfunction "VDD_RX_194") (pintype "power_in"))
      (node (ref "DD6") (pin "201") (pinfunction "VDD_TX_201") (pintype "power_in"))
      (node (ref "DD6") (pin "202") (pinfunction "VDD_TX_202") (pintype "power_in"))
      (node (ref "DD6") (pin "25") (pinfunction "VDD_RX_25") (pintype "power_in"))
      (node (ref "DD6") (pin "28") (pinfunction "VDD_RX_28") (pintype "power_in"))
      (node (ref "DD6") (pin "36") (pinfunction "VDD_TX_36") (pintype "power_in"))
      (node (ref "DD6") (pin "37") (pinfunction "VDD_TX_37") (pintype "power_in"))
      (node (ref "DD6") (pin "4") (pinfunction "VDD_RX_4") (pintype "power_in"))
      (node (ref "DD6") (pin "49") (pinfunction "VDD_RX_49") (pintype "power_in"))
      (node (ref "DD6") (pin "52") (pinfunction "VDD_RX_52") (pintype "power_in"))
      (node (ref "DD6") (pin "59") (pinfunction "VDD_TX_59") (pintype "power_in"))
      (node (ref "DD6") (pin "60") (pinfunction "VDD_TX_60") (pintype "power_in"))
      (node (ref "DD6") (pin "67") (pinfunction "VDD_RX_67") (pintype "power_in"))
      (node (ref "DD6") (pin "74") (pinfunction "VDD_RCV_74") (pintype "power_in"))
      (node (ref "DD6") (pin "75") (pinfunction "VDD_RCV_75") (pintype "power_in"))
      (node (ref "DD6") (pin "78") (pinfunction "VDD_RCV_78") (pintype "power_in"))
      (node (ref "DD6") (pin "79") (pinfunction "VDD_RCV_79") (pintype "power_in"))
      (node (ref "T1") (pin "13") (pinfunction "CT2_13") (pintype "passive"))
      (node (ref "T1") (pin "18") (pinfunction "CT1_18") (pintype "passive"))
      (node (ref "T1") (pin "3") (pinfunction "CT4_3") (pintype "passive"))
      (node (ref "T1") (pin "8") (pinfunction "CT3_8") (pintype "passive"))
    )
    (net (code "2") (name "+2BD") (class "Default")
      (node (ref "C46") (pin "2") (pinfunction "2_2") (pintype "passive"))
      (node (ref "C47") (pin "2") (pinfunction "2_2") (pintype "passive"))
      (node (ref "C48") (pin "2") (pinfunction "2_2") (pintype "passive"))
      (node (ref "C49") (pin "2") (pinfunction "2_2") (pintype "passive"))
      (node (ref "C58") (pin "1") (pinfunction "1_1") (pintype "passive"))
      (node (ref "C59") (pin "1") (pinfunction "1_1") (pintype "passive"))
      (node (ref "C60") (pin "1") (pinfunction "1_1") (pintype "passive"))
      (node (ref "DD6") (pin "108") (pinfunction "VDD_108") (pintype "power_in"))
      (node (ref "DD6") (pin "135") (pinfunction "VDD_135") (pintype "power_in"))
      (node (ref "DD6") (pin "156") (pinfunction "IO_SWM_156") (pintype "power_in"))
      (node (ref "DD6") (pin "157") (pinfunction "VDD_157") (pintype "power_in"))
      (node (ref "DD6") (pin "170") (pinfunction "PRSV_170") (pintype "power_in"))
      (node (ref "DD6") (pin "94") (pinfunction "VDD_94") (pintype "power_in"))
      (node (ref "R51") (pin "1") (pinfunction "1_1") (pintype "passive"))
    )
    (net (code "3") (name "+3,3BD") (class "Default")
      (node (ref "C79") (pin "2") (pinfunction "2_2") (pintype "passive"))
      (node (ref "C88") (pin "2") (pinfunction "2_2") (pintype "passive"))
      (node (ref "C89") (pin "2") (pinfunction "2_2") (pintype "passive"))
      (node (ref "DD6") (pin "105") (pinfunction "VDD_IO_105") (pintype "power_in"))
      (node (ref "DD6") (pin "125") (pinfunction "VDD_IO_125") (pintype "power_in"))
      (node (ref "DD6") (pin "148") (pinfunction "VDD_IO_148") (pintype "power_in"))
      (node (ref "DD7") (pin "8") (pinfunction "VCC_8") (pintype "power_in"))
      (node (ref "G2") (pin "4") (pinfunction "VCC_4") (pintype "power_in"))
      (node (ref "R39") (pin "1") (pinfunction "1_1") (pintype "passive"))
      (node (ref "R40") (pin "2") (pinfunction "2_2") (pintype "passive"))
      (node (ref "R41") (pin "2") (pinfunction "2_2") (pintype "passive"))
      (node (ref "R48") (pin "2") (pinfunction "2_2") (pintype "passive"))
      (node (ref "R50") (pin "2") (pinfunction "2_2") (pintype "passive"))
      (node (ref "VD10") (pin "2") (pinfunction "A_2") (pintype "passive"))
      (node (ref "VD11") (pin "2") (pinfunction "A_2") (pintype "passive"))
      (node (ref "VD12") (pin "2") (pinfunction "A_2") (pintype "passive"))
      (node (ref "VD13") (pin "2") (pinfunction "A_2") (pintype "passive"))
      (node (ref "VD14") (pin "2") (pinfunction "A_2") (pintype "passive"))
      (node (ref "VD15") (pin "2") (pinfunction "A_2") (pintype "passive"))
      (node (ref "VD16") (pin "2") (pinfunction "A_2") (pintype "passive"))
      (node (ref "VD2") (pin "2") (pinfunction "A_2") (pintype "passive"))
      (node (ref "VD3") (pin "2") (pinfunction "A_2") (pintype "passive"))
      (node (ref "VD4") (pin "2") (pinfunction "A_2") (pintype "passive"))
      (node (ref "VD5") (pin "2") (pinfunction "A_2") (pintype "passive"))
      (node (ref "VD6") (pin "2") (pinfunction "A_2") (pintype "passive"))
      (node (ref "VD7") (pin "2") (pinfunction "A_2") (pintype "passive"))
      (node (ref "VD8") (pin "2") (pinfunction "A_2") (pintype "passive"))
      (node (ref "VD9") (pin "2") (pinfunction "A_2") (pintype "passive"))
    )
    (net (code "4") (name "+48B") (class "Default")
      (node (ref "X5") (pin "4") (pinfunction "4_4") (pintype "passive"))
      (node (ref "X5") (pin "5") (pinfunction "5_5") (pintype "passive"))
      (node (ref "X6") (pin "4") (pinfunction "4_4") (pintype "passive"))
      (node (ref "X6") (pin "5") (pinfunction "5_5") (pintype "passive"))
      (node (ref "X7") (pin "4") (pinfunction "4_4") (pintype "passive"))
      (node (ref "X7") (pin "5") (pinfunction "5_5") (pintype "passive"))
      (node (ref "X8") (pin "4") (pinfunction "4_4") (pintype "passive"))
      (node (ref "X8") (pin "5") (pinfunction "5_5") (pintype "passive"))
    )
    (net (code "5") (name "/CMT1") (class "Default")
      (node (ref "R77") (pin "1") (pinfunction "1_1") (pintype "passive"))
      (node (ref "T1") (pin "38") (pinfunction "CMGND_38") (pintype "passive"))
    )
    (net (code "6") (name "/CMT2") (class "Default")
      (node (ref "R84") (pin "1") (pinfunction "1_1") (pintype "passive"))
      (node (ref "T1") (pin "33") (pinfunction "CMGND_33") (pintype "passive"))
    )
    (net (code "7") (name "/CMT3") (class "Default")
      (node (ref "R87") (pin "1") (pinfunction "1_1") (pintype "passive"))
      (node (ref "T1") (pin "28") (pinfunction "CMGND_28") (pintype "passive"))
    )
    (net (code "8") (name "/CMT4") (class "Default")
      (node (ref "R90") (pin "1") (pinfunction "1_1") (pintype "passive"))
      (node (ref "T1") (pin "23") (pinfunction "CMGND_23") (pintype "passive"))
    )
    (net (code "9") (name "/LED_COLLISION_1") (class "Default")
      (node (ref "DD6") (pin "112") (pinfunction "LED[1][2]_112") (pintype "power_in"))
      (node (ref "R32") (pin "2") (pinfunction "2_2") (pintype "passive"))
    )
    (net (code "10") (name "/LED_COLLISION_2") (class "Default")
      (node (ref "DD6") (pin "116") (pinfunction "LED[2][2]_116") (pintype "power_in"))
      (node (ref "R21") (pin "2") (pinfunction "2_2") (pintype "passive"))
    )
    (net (code "11") (name "/LED_COLLISION_3") (class "Default")
      (node (ref "DD6") (pin "128") (pinfunction "LED[3][2]_128") (pintype "power_in"))
      (node (ref "R25") (pin "2") (pinfunction "2_2") (pintype "passive"))
    )
    (net (code "12") (name "/LED_COLLISION_4") (class "Default")
      (node (ref "DD6") (pin "132") (pinfunction "LED[4][2]_132") (pintype "power_in"))
      (node (ref "R29") (pin "2") (pinfunction "2_2") (pintype "passive"))
    )
    (net (code "13") (name "/LED_COLLISION_5") (class "Default")
      (node (ref "DD6") (pin "138") (pinfunction "LED[5][2]_138") (pintype "power_in"))
      (node (ref "R33") (pin "2") (pinfunction "2_2") (pintype "passive"))
    )
    (net (code "14") (name "/LED_LINK_1") (class "Default")
      (node (ref "DD6") (pin "111") (pinfunction "LED[1][3]_111") (pintype "power_in"))
      (node (ref "R18") (pin "2") (pinfunction "2_2") (pintype "passive"))
    )
    (net (code "15") (name "/LED_LINK_2") (class "Default")
      (node (ref "DD6") (pin "115") (pinfunction "LED[2][3]_115") (pintype "power_in"))
      (node (ref "R22") (pin "2") (pinfunction "2_2") (pintype "passive"))
    )
    (net (code "16") (name "/LED_LINK_3") (class "Default")
      (node (ref "DD6") (pin "127") (pinfunction "LED[3][3]_127") (pintype "power_in"))
      (node (ref "R19") (pin "2") (pinfunction "2_2") (pintype "passive"))
    )
    (net (code "17") (name "/LED_LINK_4") (class "Default")
      (node (ref "DD6") (pin "131") (pinfunction "LED[4][3]_131") (pintype "power_in"))
      (node (ref "R23") (pin "2") (pinfunction "2_2") (pintype "passive"))
    )
    (net (code "18") (name "/LED_LINK_5") (class "Default")
      (node (ref "DD6") (pin "137") (pinfunction "LED[5][3]_137") (pintype "power_in"))
      (node (ref "R26") (pin "2") (pinfunction "2_2") (pintype "passive"))
    )
    (net (code "19") (name "/LED_SPEED_1") (class "Default")
      (node (ref "DD6") (pin "114") (pinfunction "LED[1][0]_114") (pintype "power_in"))
      (node (ref "R27") (pin "2") (pinfunction "2_2") (pintype "passive"))
    )
    (net (code "20") (name "/LED_SPEED_2") (class "Default")
      (node (ref "DD6") (pin "118") (pinfunction "LED[2][0]_118") (pintype "power_in"))
      (node (ref "R31") (pin "2") (pinfunction "2_2") (pintype "passive"))
    )
    (net (code "21") (name "/LED_SPEED_3") (class "Default")
      (node (ref "DD6") (pin "130") (pinfunction "LED[3][0]_130") (pintype "power_in"))
      (node (ref "R20") (pin "2") (pinfunction "2_2") (pintype "passive"))
    )
    (net (code "22") (name "/LED_SPEED_4") (class "Default")
      (node (ref "DD6") (pin "134") (pinfunction "LED[4][0]_134") (pintype "power_in"))
      (node (ref "R24") (pin "2") (pinfunction "2_2") (pintype "passive"))
    )
    (net (code "23") (name "/LED_SPEED_5") (class "Default")
      (node (ref "DD6") (pin "140") (pinfunction "LED[5][0]_140") (pintype "power_in"))
      (node (ref "R28") (pin "2") (pinfunction "2_2") (pintype "passive"))
    )
    (net (code "24") (name "/RASP_ETH_RX_N") (class "Default")
      (node (ref "DD6") (pin "6") (pinfunction "RXM[3]_6") (pintype "power_in"))
    )
    (net (code "25") (name "/RASP_ETH_RX_P") (class "Default")
      (node (ref "DD6") (pin "5") (pinfunction "RXP[3]_5") (pintype "power_in"))
    )
    (net (code "26") (name "/RASP_ETH_TX_N") (class "Default")
      (node (ref "DD6") (pin "10") (pinfunction "TXM[3]_10") (pintype "power_in"))
    )
    (net (code "27") (name "/RASP_ETH_TX_P") (class "Default")
      (node (ref "DD6") (pin "9") (pinfunction "TXP[3]_9") (pintype "power_in"))
    )
    (net (code "28") (name "/RX+_CAMB") (class "Default")
      (node (ref "T1") (pin "29") (pinfunction "TX2-_29") (pintype "passive"))
      (node (ref "X6") (pin "1") (pinfunction "1_1") (pintype "passive"))
    )
    (net (code "29") (name "/RX+_CAMF") (class "Default")
      (node (ref "T1") (pin "21") (pinfunction "TX1+_21") (pintype "passive"))
      (node (ref "X5") (pin "1") (pinfunction "1_1") (pintype "passive"))
    )
    (net (code "30") (name "/RX+_DIAGN") (class "Default")
      (node (ref "T1") (pin "34") (pinfunction "RX3+_34") (pintype "passive"))
      (node (ref "X8") (pin "1") (pinfunction "1_1") (pintype "passive"))
    )
    (net (code "31") (name "/RX+_OPTO") (class "Default")
      (node (ref "T1") (pin "36") (pinfunction "RX4-_36") (pintype "passive"))
      (node (ref "X7") (pin "1") (pinfunction "1_1") (pintype "passive"))
    )
    (net (code "32") (name "/RX-_CAMB") (class "Default")
      (node (ref "T1") (pin "30") (pinfunction "TX2+_30") (pintype "passive"))
      (node (ref "X6") (pin "2") (pinfunction "2_2") (pintype "passive"))
    )
    (net (code "33") (name "/RX-_CAMF") (class "Default")
      (node (ref "T1") (pin "22") (pinfunction "TX1-_22") (pintype "passive"))
      (node (ref "X5") (pin "2") (pinfunction "2_2") (pintype "passive"))
    )
    (net (code "34") (name "/RX-_DIAGN") (class "Default")
      (node (ref "T1") (pin "35") (pinfunction "RX3-_35") (pintype "passive"))
      (node (ref "X8") (pin "2") (pinfunction "2_2") (pintype "passive"))
    )
    (net (code "35") (name "/RX-_OPTO") (class "Default")
      (node (ref "T1") (pin "37") (pinfunction "RX4+_37") (pintype "passive"))
      (node (ref "X7") (pin "2") (pinfunction "2_2") (pintype "passive"))
    )
    (net (code "36") (name "/RXM_CAMB") (class "Default")
      (node (ref "DD6") (pin "207") (pinfunction "RXM[2]_207") (pintype "power_in"))
      (node (ref "R91") (pin "2") (pinfunction "2_2") (pintype "passive"))
      (node (ref "T1") (pin "11") (pinfunction "TD2+_11") (pintype "passive"))
    )
    (net (code "37") (name "/RXM_CAMF") (class "Default")
      (node (ref "DD6") (pin "197") (pinfunction "RXM[1]_197") (pintype "power_in"))
      (node (ref "R79") (pin "2") (pinfunction "2_2") (pintype "passive"))
      (node (ref "T1") (pin "19") (pinfunction "TD1-_19") (pintype "passive"))
    )
    (net (code "38") (name "/RXM_DIAGN") (class "Default")
      (node (ref "DD6") (pin "23") (pinfunction "RXM[4]_23") (pintype "power_in"))
      (node (ref "R92") (pin "2") (pinfunction "2_2") (pintype "passive"))
      (node (ref "T1") (pin "6") (pinfunction "RD3-_6") (pintype "passive"))
    )
    (net (code "39") (name "/RXM_OPTO") (class "Default")
      (node (ref "DD6") (pin "31") (pinfunction "RXM[5]_31") (pintype "power_in"))
      (node (ref "R80") (pin "2") (pinfunction "2_2") (pintype "passive"))
      (node (ref "T1") (pin "4") (pinfunction "RD4+_4") (pintype "passive"))
    )
    (net (code "40") (name "/RXP_CAMB") (class "Default")
      (node (ref "DD6") (pin "206") (pinfunction "RXP[2]_206") (pintype "power_in"))
      (node (ref "R88") (pin "2") (pinfunction "2_2") (pintype "passive"))
      (node (ref "T1") (pin "12") (pinfunction "TD2-_12") (pintype "passive"))
    )
    (net (code "41") (name "/RXP_CAMF") (class "Default")
      (node (ref "DD6") (pin "196") (pinfunction "RXP[1]_196") (pintype "power_in"))
      (node (ref "R74") (pin "2") (pinfunction "2_2") (pintype "passive"))
      (node (ref "T1") (pin "20") (pinfunction "TD1+_20") (pintype "passive"))
    )
    (net (code "42") (name "/RXP_DIAGN") (class "Default")
      (node (ref "DD6") (pin "22") (pinfunction "RXP[4]_22") (pintype "power_in"))
      (node (ref "R89") (pin "2") (pinfunction "2_2") (pintype "passive"))
      (node (ref "T1") (pin "7") (pinfunction "RD3+_7") (pintype "passive"))
    )
    (net (code "43") (name "/RXP_OPTO") (class "Default")
      (node (ref "DD6") (pin "30") (pinfunction "RXP[5]_30") (pintype "power_in"))
      (node (ref "R75") (pin "2") (pinfunction "2_2") (pintype "passive"))
      (node (ref "T1") (pin "5") (pinfunction "RD4-_5") (pintype "passive"))
    )
    (net (code "44") (name "/SCL") (class "Default")
      (node (ref "DD6") (pin "93") (pinfunction "SCL_93") (pintype "power_in"))
      (node (ref "DD7") (pin "6") (pinfunction "SCL_6") (pintype "power_in"))
      (node (ref "R40") (pin "1") (pinfunction "1_1") (pintype "passive"))
    )
    (net (code "45") (name "/SDA") (class "Default")
      (node (ref "DD6") (pin "92") (pinfunction "SDA_92") (pintype "power_in"))
      (node (ref "DD7") (pin "5") (pinfunction "SDA_5") (pintype "power_in"))
      (node (ref "R41") (pin "1") (pinfunction "1_1") (pintype "passive"))
    )
    (net (code "46") (name "/TX+_CAMB") (class "Default")
      (node (ref "T1") (pin "26") (pinfunction "RX2-_26") (pintype "passive"))
      (node (ref "X6") (pin "3") (pinfunction "3_3") (pintype "passive"))
    )
    (net (code "47") (name "/TX+_CAMF") (class "Default")
      (node (ref "T1") (pin "24") (pinfunction "RX1+_24") (pintype "passive"))
      (node (ref "X5") (pin "3") (pinfunction "3_3") (pintype "passive"))
    )
    (net (code "48") (name "/TX+_DIAGN") (class "Default")
      (node (ref "T1") (pin "31") (pinfunction "TX3+_31") (pintype "passive"))
      (node (ref "X8") (pin "3") (pinfunction "3_3") (pintype "passive"))
    )
    (net (code "49") (name "/TX+_OPTO") (class "Default")
      (node (ref "T1") (pin "39") (pinfunction "TX4-_39") (pintype "passive"))
      (node (ref "X7") (pin "3") (pinfunction "3_3") (pintype "passive"))
    )
    (net (code "50") (name "/TX-_CAMB") (class "Default")
      (node (ref "T1") (pin "27") (pinfunction "RX2+_27") (pintype "passive"))
      (node (ref "X6") (pin "6") (pinfunction "6_6") (pintype "passive"))
    )
    (net (code "51") (name "/TX-_CAMF") (class "Default")
      (node (ref "T1") (pin "25") (pinfunction "RX1-_25") (pintype "passive"))
      (node (ref "X5") (pin "6") (pinfunction "6_6") (pintype "passive"))
    )
    (net (code "52") (name "/TX-_DIAGN") (class "Default")
      (node (ref "T1") (pin "32") (pinfunction "TX3-_32") (pintype "passive"))
      (node (ref "X8") (pin "6") (pinfunction "6_6") (pintype "passive"))
    )
    (net (code "53") (name "/TX-_OPTO") (class "Default")
      (node (ref "T1") (pin "40") (pinfunction "TX4+_40") (pintype "passive"))
      (node (ref "X7") (pin "6") (pinfunction "6_6") (pintype "passive"))
    )
    (net (code "54") (name "/TXM_CAMB") (class "Default")
      (node (ref "DD6") (pin "204") (pinfunction "TXM[2]_204") (pintype "power_in"))
      (node (ref "R85") (pin "2") (pinfunction "2_2") (pintype "passive"))
      (node (ref "T1") (pin "14") (pinfunction "RD2+_14") (pintype "passive"))
    )
    (net (code "55") (name "/TXM_CAMF") (class "Default")
      (node (ref "DD6") (pin "200") (pinfunction "TXM[1]_200") (pintype "power_in"))
      (node (ref "R70") (pin "2") (pinfunction "2_2") (pintype "passive"))
      (node (ref "T1") (pin "16") (pinfunction "RD1-_16") (pintype "passive"))
    )
    (net (code "56") (name "/TXM_DIAGN") (class "Default")
      (node (ref "DD6") (pin "20") (pinfunction "TXM[4]_20") (pintype "power_in"))
      (node (ref "R86") (pin "2") (pinfunction "2_2") (pintype "passive"))
      (node (ref "T1") (pin "9") (pinfunction "TD3-_9") (pintype "passive"))
    )
    (net (code "57") (name "/TXM_OPTO") (class "Default")
      (node (ref "DD6") (pin "34") (pinfunction "TXM[5]_34") (pintype "power_in"))
      (node (ref "R71") (pin "2") (pinfunction "2_2") (pintype "passive"))
      (node (ref "T1") (pin "1") (pinfunction "TD4+_1") (pintype "passive"))
    )
    (net (code "58") (name "/TXP_CAMB") (class "Default")
      (node (ref "DD6") (pin "203") (pinfunction "TXP[2]_203") (pintype "power_in"))
      (node (ref "R82") (pin "2") (pinfunction "2_2") (pintype "passive"))
      (node (ref "T1") (pin "15") (pinfunction "RD2-_15") (pintype "passive"))
    )
    (net (code "59") (name "/TXP_CAMF") (class "Default")
      (node (ref "DD6") (pin "199") (pinfunction "TXP[1]_199") (pintype "power_in"))
      (node (ref "R66") (pin "2") (pinfunction "2_2") (pintype "passive"))
      (node (ref "T1") (pin "17") (pinfunction "RD1+_17") (pintype "passive"))
    )
    (net (code "60") (name "/TXP_DIAGN") (class "Default")
      (node (ref "DD6") (pin "19") (pinfunction "TXP[4]_19") (pintype "power_in"))
      (node (ref "R83") (pin "2") (pinfunction "2_2") (pintype "passive"))
      (node (ref "T1") (pin "10") (pinfunction "TD3+_10") (pintype "passive"))
    )
    (net (code "61") (name "/TXP_OPTO") (class "Default")
      (node (ref "DD6") (pin "33") (pinfunction "TXP[5]_33") (pintype "power_in"))
      (node (ref "R67") (pin "2") (pinfunction "2_2") (pintype "passive"))
      (node (ref "T1") (pin "2") (pinfunction "TD4-_2") (pintype "passive"))
    )
    (net (code "62") (name "AGND") (class "Default")
      (node (ref "C100") (pin "1") (pinfunction "1_1") (pintype "passive"))
      (node (ref "C101") (pin "2") (pinfunction "2_2") (pintype "passive"))
      (node (ref "C50") (pin "1") (pinfunction "1_1") (pintype "passive"))
      (node (ref "C51") (pin "1") (pinfunction "1_1") (pintype "passive"))
      (node (ref "C52") (pin "1") (pinfunction "1_1") (pintype "passive"))
      (node (ref "C53") (pin "1") (pinfunction "1_1") (pintype "passive"))
      (node (ref "C54") (pin "1") (pinfunction "1_1") (pintype "passive"))
      (node (ref "C55") (pin "1") (pinfunction "1_1") (pintype "passive"))
      (node (ref "C56") (pin "1") (pinfunction "1_1") (pintype "passive"))
      (node (ref "C57") (pin "1") (pinfunction "1_1") (pintype "passive"))
      (node (ref "C61") (pin "2") (pinfunction "2_2") (pintype "passive"))
      (node (ref "C62") (pin "2") (pinfunction "2_2") (pintype "passive"))
      (node (ref "C63") (pin "2") (pinfunction "2_2") (pintype "passive"))
      (node (ref "C64") (pin "2") (pinfunction "2_2") (pintype "passive"))
      (node (ref "C65") (pin "2") (pinfunction "2_2") (pintype "passive"))
      (node (ref "C66") (pin "2") (pinfunction "2_2") (pintype "passive"))
      (node (ref "C67") (pin "2") (pinfunction "2_2") (pintype "passive"))
      (node (ref "C68") (pin "2") (pinfunction "2_2") (pintype "passive"))
      (node (ref "C69") (pin "1") (pinfunction "1_1") (pintype "passive"))
      (node (ref "C70") (pin "1") (pinfunction "1_1") (pintype "passive"))
      (node (ref "C71") (pin "1") (pinfunction "1_1") (pintype "passive"))
      (node (ref "C72") (pin "1") (pinfunction "1_1") (pintype "passive"))
      (node (ref "C73") (pin "1") (pinfunction "1_1") (pintype "passive"))
      (node (ref "C74") (pin "1") (pinfunction "1_1") (pintype "passive"))
      (node (ref "C75") (pin "1") (pinfunction "1_1") (pintype "passive"))
      (node (ref "C76") (pin "1") (pinfunction "1_1") (pintype "passive"))
      (node (ref "C80") (pin "1") (pinfunction "1_1") (pintype "passive"))
      (node (ref "C87") (pin "1") (pinfunction "1_1") (pintype "passive"))
      (node (ref "C90") (pin "1") (pinfunction "1_1") (pintype "passive"))
      (node (ref "C91") (pin "1") (pinfunction "1_1") (pintype "passive"))
      (node (ref "C92") (pin "1") (pinfunction "1_1") (pintype "passive"))
      (node (ref "C93") (pin "1") (pinfunction "1_1") (pintype "passive"))
      (node (ref "C94") (pin "2") (pinfunction "2_2") (pintype "passive"))
      (node (ref "C95") (pin "2") (pinfunction "2_2") (pintype "passive"))
      (node (ref "C96") (pin "1") (pinfunction "1_1") (pintype "passive"))
      (node (ref "C97") (pin "1") (pinfunction "1_1") (pintype "passive"))
      (node (ref "C98") (pin "2") (pinfunction "2_2") (pintype "passive"))
      (node (ref "C99") (pin "1") (pinfunction "1_1") (pintype "passive"))
      (node (ref "DD6") (pin "15") (pinfunction "GND_TX_15") (pintype "power_in"))
      (node (ref "DD6") (pin "179") (pinfunction "GND_PLLTX_179") (pintype "power_in"))
      (node (ref "DD6") (pin "18") (pinfunction "GND_ISO_18") (pintype "power_in"))
      (node (ref "DD6") (pin "184") (pinfunction "GND_RCV_184") (pintype "power_in"))
      (node (ref "DD6") (pin "185") (pinfunction "GND_RCV_185") (pintype "power_in"))
      (node (ref "DD6") (pin "188") (pinfunction "GND_RCV_188") (pintype "power_in"))
      (node (ref "DD6") (pin "189") (pinfunction "GND_RCV_189") (pintype "power_in"))
      (node (ref "DD6") (pin "195") (pinfunction "GND_RX_195") (pintype "power_in"))
      (node (ref "DD6") (pin "198") (pinfunction "GND_TX_198") (pintype "power_in"))
      (node (ref "DD6") (pin "2") (pinfunction "GND_RX_2") (pintype "power_in"))
      (node (ref "DD6") (pin "205") (pinfunction "GND_TX_205") (pintype "power_in"))
      (node (ref "DD6") (pin "208") (pinfunction "GND_ISO_208") (pintype "power_in"))
      (node (ref "DD6") (pin "21") (pinfunction "GND_TX_21") (pintype "power_in"))
      (node (ref "DD6") (pin "24") (pinfunction "GND_RX_24") (pintype "power_in"))
      (node (ref "DD6") (pin "27") (pinfunction "GND_ISO_27") (pintype "power_in"))
      (node (ref "DD6") (pin "29") (pinfunction "GND_RX_29") (pintype "power_in"))
      (node (ref "DD6") (pin "3") (pinfunction "GND_RX_3") (pintype "power_in"))
      (node (ref "DD6") (pin "32") (pinfunction "GND_TX_32") (pintype "power_in"))
      (node (ref "DD6") (pin "35") (pinfunction "GND_ISO_35") (pintype "power_in"))
      (node (ref "DD6") (pin "38") (pinfunction "GND_TX_38") (pintype "power_in"))
      (node (ref "DD6") (pin "50") (pinfunction "GND_RX_50") (pintype "power_in"))
      (node (ref "DD6") (pin "51") (pinfunction "GND_RX_51") (pintype "power_in"))
      (node (ref "DD6") (pin "53") (pinfunction "GND_ISO_53") (pintype "power_in"))
      (node (ref "DD6") (pin "56") (pinfunction "GND_TX_56") (pintype "power_in"))
      (node (ref "DD6") (pin "63") (pinfunction "GND_TX_63") (pintype "power_in"))
      (node (ref "DD6") (pin "66") (pinfunction "GND_RX_66") (pintype "power_in"))
      (node (ref "DD6") (pin "72") (pinfunction "GND_RCV_72") (pintype "power_in"))
      (node (ref "DD6") (pin "73") (pinfunction "GND_RCV_73") (pintype "power_in"))
      (node (ref "DD6") (pin "76") (pinfunction "GND_RCV_76") (pintype "power_in"))
      (node (ref "DD6") (pin "77") (pinfunction "GND_RCV_77") (pintype "power_in"))
      (node (ref "R52") (pin "2") (pinfunction "2_2") (pintype "passive"))
      (node (ref "R65") (pin "2") (pinfunction "2_2") (pintype "passive"))
      (node (ref "R68") (pin "2") (pinfunction "2_2") (pintype "passive"))
      (node (ref "R69") (pin "2") (pinfunction "2_2") (pintype "passive"))
      (node (ref "R72") (pin "2") (pinfunction "2_2") (pintype "passive"))
      (node (ref "R73") (pin "2") (pinfunction "2_2") (pintype "passive"))
      (node (ref "R76") (pin "2") (pinfunction "2_2") (pintype "passive"))
      (node (ref "R78") (pin "2") (pinfunction "2_2") (pintype "passive"))
      (node (ref "R81") (pin "2") (pinfunction "2_2") (pintype "passive"))
    )
    (net (code "63") (name "DGND") (class "Default")
      (node (ref "C46") (pin "1") (pinfunction "1_1") (pintype "passive"))
      (node (ref "C47") (pin "1") (pinfunction "1_1") (pintype "passive"))
      (node (ref "C48") (pin "1") (pinfunction "1_1") (pintype "passive"))
      (node (ref "C49") (pin "1") (pinfunction "1_1") (pintype "passive"))
      (node (ref "C58") (pin "2") (pinfunction "2_2") (pintype "passive"))
      (node (ref "C59") (pin "2") (pinfunction "2_2") (pintype "passive"))
      (node (ref "C60") (pin "2") (pinfunction "2_2") (pintype "passive"))
      (node (ref "C79") (pin "1") (pinfunction "1_1") (pintype "passive"))
      (node (ref "C88") (pin "1") (pinfunction "1_1") (pintype "passive"))
      (node (ref "C89") (pin "1") (pinfunction "1_1") (pintype "passive"))
      (node (ref "DD6") (pin "106") (pinfunction "GND_106") (pintype "power_in"))
      (node (ref "DD6") (pin "107") (pinfunction "GND_107") (pintype "power_in"))
      (node (ref "DD6") (pin "109") (pinfunction "BIST_109") (pintype "power_in"))
      (node (ref "DD6") (pin "126") (pinfunction "GND_126") (pintype "power_in"))
      (node (ref "DD6") (pin "136") (pinfunction "GND_136") (pintype "power_in"))
      (node (ref "DD6") (pin "154") (pinfunction "GND_154") (pintype "power_in"))
      (node (ref "DD6") (pin "155") (pinfunction "GND_155") (pintype "power_in"))
      (node (ref "DD6") (pin "162") (pinfunction "MIIS[1]_162") (pintype "power_in"))
      (node (ref "DD6") (pin "163") (pinfunction "MIIS[0]_163") (pintype "power_in"))
      (node (ref "DD6") (pin "164") (pinfunction "MODESEL[3]_164") (pintype "power_in"))
      (node (ref "DD6") (pin "165") (pinfunction "MODESEL[2]_165") (pintype "power_in"))
      (node (ref "DD6") (pin "166") (pinfunction "MODESEL[1]_166") (pintype "power_in"))
      (node (ref "DD6") (pin "167") (pinfunction "MODESEL[0]_167") (pintype "power_in"))
      (node (ref "DD6") (pin "168") (pinfunction "TESTEN_168") (pintype "power_in"))
      (node (ref "DD6") (pin "169") (pinfunction "SCANEN_169") (pintype "power_in"))
      (node (ref "DD6") (pin "82") (pinfunction "RLPBK_82") (pintype "power_in"))
      (node (ref "DD6") (pin "95") (pinfunction "GND_95") (pintype "power_in"))
      (node (ref "DD7") (pin "1") (pinfunction "A0_1") (pintype "power_in"))
      (node (ref "DD7") (pin "2") (pinfunction "A1_2") (pintype "power_in"))
      (node (ref "DD7") (pin "3") (pinfunction "A2_3") (pintype "power_in"))
      (node (ref "DD7") (pin "4") (pinfunction "GND_4") (pintype "power_in"))
      (node (ref "DD7") (pin "7") (pinfunction "WP_7") (pintype "power_in"))
      (node (ref "G2") (pin "2") (pinfunction "GND_2") (pintype "power_in"))
      (node (ref "R49") (pin "2") (pinfunction "2_2") (pintype "passive"))
      (node (ref "SW1") (pin "1") (pintype "passive"))
      (node (ref "SW2") (pin "2") (pintype "passive"))
      (node (ref "SW3") (pin "2") (pintype "passive"))
    )
    (net (code "64") (name "EGND") (class "Default")
      (node (ref "X5") (pin "9") (pinfunction "9_9") (pintype "passive"))
      (node (ref "X6") (pin "9") (pinfunction "9_9") (pintype "passive"))
      (node (ref "X7") (pin "9") (pinfunction "9_9") (pintype "passive"))
      (node (ref "X8") (pin "9") (pinfunction "9_9") (pintype "passive"))
    )
    (net (code "65") (name "Net-(C90-Pad2)") (class "Default")
      (node (ref "C90") (pin "2") (pinfunction "2_2") (pintype "passive"))
      (node (ref "R66") (pin "1") (pinfunction "1_1") (pintype "passive"))
      (node (ref "R70") (pin "1") (pinfunction "1_1") (pintype "passive"))
    )
    (net (code "66") (name "Net-(C91-Pad2)") (class "Default")
      (node (ref "C91") (pin "2") (pinfunction "2_2") (pintype "passive"))
      (node (ref "R67") (pin "1") (pinfunction "1_1") (pintype "passive"))
      (node (ref "R71") (pin "1") (pinfunction "1_1") (pintype "passive"))
    )
    (net (code "67") (name "Net-(C92-Pad2)") (class "Default")
      (node (ref "C92") (pin "2") (pinfunction "2_2") (pintype "passive"))
      (node (ref "R74") (pin "1") (pinfunction "1_1") (pintype "passive"))
      (node (ref "R79") (pin "1") (pinfunction "1_1") (pintype "passive"))
    )
    (net (code "68") (name "Net-(C93-Pad2)") (class "Default")
      (node (ref "C93") (pin "2") (pinfunction "2_2") (pintype "passive"))
      (node (ref "R75") (pin "1") (pinfunction "1_1") (pintype "passive"))
      (node (ref "R80") (pin "1") (pinfunction "1_1") (pintype "passive"))
    )
    (net (code "69") (name "Net-(C94-Pad1)") (class "Default")
      (node (ref "C94") (pin "1") (pinfunction "1_1") (pintype "passive"))
      (node (ref "R77") (pin "2") (pinfunction "2_2") (pintype "passive"))
    )
    (net (code "70") (name "Net-(C95-Pad1)") (class "Default")
      (node (ref "C95") (pin "1") (pinfunction "1_1") (pintype "passive"))
      (node (ref "R84") (pin "2") (pinfunction "2_2") (pintype "passive"))
    )
    (net (code "71") (name "Net-(C96-Pad2)") (class "Default")
      (node (ref "C96") (pin "2") (pinfunction "2_2") (pintype "passive"))
      (node (ref "R82") (pin "1") (pinfunction "1_1") (pintype "passive"))
      (node (ref "R85") (pin "1") (pinfunction "1_1") (pintype "passive"))
    )
    (net (code "72") (name "Net-(C97-Pad2)") (class "Default")
      (node (ref "C97") (pin "2") (pinfunction "2_2") (pintype "passive"))
      (node (ref "R83") (pin "1") (pinfunction "1_1") (pintype "passive"))
      (node (ref "R86") (pin "1") (pinfunction "1_1") (pintype "passive"))
    )
    (net (code "73") (name "Net-(C98-Pad1)") (class "Default")
      (node (ref "C98") (pin "1") (pinfunction "1_1") (pintype "passive"))
      (node (ref "R87") (pin "2") (pinfunction "2_2") (pintype "passive"))
    )
    (net (code "74") (name "Net-(C99-Pad2)") (class "Default")
      (node (ref "C99") (pin "2") (pinfunction "2_2") (pintype "passive"))
      (node (ref "R88") (pin "1") (pinfunction "1_1") (pintype "passive"))
      (node (ref "R91") (pin "1") (pinfunction "1_1") (pintype "passive"))
    )
    (net (code "75") (name "Net-(C100-Pad2)") (class "Default")
      (node (ref "C100") (pin "2") (pinfunction "2_2") (pintype "passive"))
      (node (ref "R89") (pin "1") (pinfunction "1_1") (pintype "passive"))
      (node (ref "R92") (pin "1") (pinfunction "1_1") (pintype "passive"))
    )
    (net (code "76") (name "Net-(C101-Pad1)") (class "Default")
      (node (ref "C101") (pin "1") (pinfunction "1_1") (pintype "passive"))
      (node (ref "R90") (pin "2") (pinfunction "2_2") (pintype "passive"))
    )
    (net (code "77") (name "Net-(DD6A-X1_IN)") (class "Default")
      (node (ref "DD6") (pin "176") (pinfunction "X1_IN_176") (pintype "power_in"))
      (node (ref "G2") (pin "3") (pinfunction "DCLK_3") (pintype "power_in"))
    )
    (net (code "78") (name "Net-(DD6B-CFGMODE)") (class "Default")
      (node (ref "DD6") (pin "171") (pinfunction "CFGMODE_171") (pintype "power_in"))
      (node (ref "R39") (pin "2") (pinfunction "2_2") (pintype "passive"))
      (node (ref "SW1") (pin "2") (pintype "passive"))
    )
    (net (code "79") (name "Net-(DD6B-FXSD[1])") (class "Default")
      (node (ref "DD6") (pin "190") (pinfunction "FXSD[1]_190") (pintype "power_in"))
      (node (ref "R65") (pin "1") (pinfunction "1_1") (pintype "passive"))
    )
    (net (code "80") (name "Net-(DD6B-FXSD[2])") (class "Default")
      (node (ref "DD6") (pin "191") (pinfunction "FXSD[2]_191") (pintype "power_in"))
      (node (ref "R68") (pin "1") (pinfunction "1_1") (pintype "passive"))
    )
    (net (code "81") (name "Net-(DD6B-FXSD[3])") (class "Default")
      (node (ref "DD6") (pin "192") (pinfunction "FXSD[3]_192") (pintype "power_in"))
      (node (ref "R69") (pin "1") (pinfunction "1_1") (pintype "passive"))
    )
    (net (code "82") (name "Net-(DD6B-FXSD[4])") (class "Default")
      (node (ref "DD6") (pin "193") (pinfunction "FXSD[4]_193") (pintype "power_in"))
      (node (ref "R72") (pin "1") (pinfunction "1_1") (pintype "passive"))
    )
    (net (code "83") (name "Net-(DD6B-FXSD[5])") (class "Default")
      (node (ref "DD6") (pin "68") (pinfunction "FXSD[5]_68") (pintype "power_in"))
      (node (ref "R73") (pin "1") (pinfunction "1_1") (pintype "passive"))
    )
    (net (code "84") (name "Net-(DD6B-FXSD[6])") (class "Default")
      (node (ref "DD6") (pin "69") (pinfunction "FXSD[6]_69") (pintype "power_in"))
      (node (ref "R76") (pin "1") (pinfunction "1_1") (pintype "passive"))
    )
    (net (code "85") (name "Net-(DD6B-FXSD[7])") (class "Default")
      (node (ref "DD6") (pin "70") (pinfunction "FXSD[7]_70") (pintype "power_in"))
      (node (ref "R78") (pin "1") (pinfunction "1_1") (pintype "passive"))
    )
    (net (code "86") (name "Net-(DD6B-FXSD[8])") (class "Default")
      (node (ref "DD6") (pin "71") (pinfunction "FXSD[8]_71") (pintype "power_in"))
      (node (ref "R81") (pin "1") (pinfunction "1_1") (pintype "passive"))
    )
    (net (code "87") (name "Net-(DD6B-T[4])") (class "Default")
      (node (ref "DD6") (pin "173") (pinfunction "T[4]_173") (pintype "power_in"))
      (node (ref "R49") (pin "1") (pinfunction "1_1") (pintype "passive"))
    )
    (net (code "88") (name "Net-(DD6C-AUTOMDIX)") (class "Default")
      (node (ref "DD6") (pin "87") (pinfunction "AUTOMDIX_87") (pintype "power_in"))
      (node (ref "R51") (pin "2") (pinfunction "2_2") (pintype "passive"))
    )
    (net (code "89") (name "Net-(DD6C-EN1P)") (class "Default")
      (node (ref "DD6") (pin "91") (pinfunction "EN1P_91") (pintype "power_in"))
      (node (ref "R48") (pin "1") (pinfunction "1_1") (pintype "passive"))
      (node (ref "SW2") (pin "1") (pintype "passive"))
    )
    (net (code "90") (name "Net-(DD6C-ISET)") (class "Default")
      (node (ref "DD6") (pin "26") (pinfunction "ISET_26") (pintype "power_in"))
      (node (ref "R52") (pin "1") (pinfunction "1_1") (pintype "passive"))
    )
    (net (code "91") (name "Net-(DD6C-RST#)") (class "Default")
      (node (ref "DD6") (pin "110") (pinfunction "RST#_110") (pintype "power_in"))
      (node (ref "R50") (pin "1") (pinfunction "1_1") (pintype "passive"))
      (node (ref "SW3") (pin "1") (pintype "passive"))
    )
    (net (code "92") (name "Net-(VD2-K)") (class "Default")
      (node (ref "R18") (pin "1") (pinfunction "1_1") (pintype "passive"))
      (node (ref "VD2") (pin "1") (pinfunction "K_1") (pintype "passive"))
    )
    (net (code "93") (name "Net-(VD3-K)") (class "Default")
      (node (ref "R19") (pin "1") (pinfunction "1_1") (pintype "passive"))
      (node (ref "VD3") (pin "1") (pinfunction "K_1") (pintype "passive"))
    )
    (net (code "94") (name "Net-(VD4-K)") (class "Default")
      (node (ref "R20") (pin "1") (pinfunction "1_1") (pintype "passive"))
      (node (ref "VD4") (pin "1") (pinfunction "K_1") (pintype "passive"))
    )
    (net (code "95") (name "Net-(VD5-K)") (class "Default")
      (node (ref "R21") (pin "1") (pinfunction "1_1") (pintype "passive"))
      (node (ref "VD5") (pin "1") (pinfunction "K_1") (pintype "passive"))
    )
    (net (code "96") (name "Net-(VD6-K)") (class "Default")
      (node (ref "R22") (pin "1") (pinfunction "1_1") (pintype "passive"))
      (node (ref "VD6") (pin "1") (pinfunction "K_1") (pintype "passive"))
    )
    (net (code "97") (name "Net-(VD7-K)") (class "Default")
      (node (ref "R23") (pin "1") (pinfunction "1_1") (pintype "passive"))
      (node (ref "VD7") (pin "1") (pinfunction "K_1") (pintype "passive"))
    )
    (net (code "98") (name "Net-(VD8-K)") (class "Default")
      (node (ref "R24") (pin "1") (pinfunction "1_1") (pintype "passive"))
      (node (ref "VD8") (pin "1") (pinfunction "K_1") (pintype "passive"))
    )
    (net (code "99") (name "Net-(VD9-K)") (class "Default")
      (node (ref "R25") (pin "1") (pinfunction "1_1") (pintype "passive"))
      (node (ref "VD9") (pin "1") (pinfunction "K_1") (pintype "passive"))
    )
    (net (code "100") (name "Net-(VD10-K)") (class "Default")
      (node (ref "R26") (pin "1") (pinfunction "1_1") (pintype "passive"))
      (node (ref "VD10") (pin "1") (pinfunction "K_1") (pintype "passive"))
    )
    (net (code "101") (name "Net-(VD11-K)") (class "Default")
      (node (ref "R27") (pin "1") (pinfunction "1_1") (pintype "passive"))
      (node (ref "VD11") (pin "1") (pinfunction "K_1") (pintype "passive"))
    )
    (net (code "102") (name "Net-(VD12-K)") (class "Default")
      (node (ref "R28") (pin "1") (pinfunction "1_1") (pintype "passive"))
      (node (ref "VD12") (pin "1") (pinfunction "K_1") (pintype "passive"))
    )
    (net (code "103") (name "Net-(VD13-K)") (class "Default")
      (node (ref "R29") (pin "1") (pinfunction "1_1") (pintype "passive"))
      (node (ref "VD13") (pin "1") (pinfunction "K_1") (pintype "passive"))
    )
    (net (code "104") (name "Net-(VD14-K)") (class "Default")
      (node (ref "R31") (pin "1") (pinfunction "1_1") (pintype "passive"))
      (node (ref "VD14") (pin "1") (pinfunction "K_1") (pintype "passive"))
    )
    (net (code "105") (name "Net-(VD15-K)") (class "Default")
      (node (ref "R32") (pin "1") (pinfunction "1_1") (pintype "passive"))
      (node (ref "VD15") (pin "1") (pinfunction "K_1") (pintype "passive"))
    )
    (net (code "106") (name "Net-(VD16-K)") (class "Default")
      (node (ref "R33") (pin "1") (pinfunction "1_1") (pintype "passive"))
      (node (ref "VD16") (pin "1") (pinfunction "K_1") (pintype "passive"))
    )
    (net (code "107") (name "PGND") (class "Default")
      (node (ref "X5") (pin "7") (pinfunction "7_7") (pintype "passive"))
      (node (ref "X5") (pin "8") (pinfunction "8_8") (pintype "passive"))
      (node (ref "X6") (pin "7") (pinfunction "7_7") (pintype "passive"))
      (node (ref "X6") (pin "8") (pinfunction "8_8") (pintype "passive"))
      (node (ref "X7") (pin "7") (pinfunction "7_7") (pintype "passive"))
      (node (ref "X7") (pin "8") (pinfunction "8_8") (pintype "passive"))
      (node (ref "X8") (pin "7") (pinfunction "7_7") (pintype "passive"))
      (node (ref "X8") (pin "8") (pinfunction "8_8") (pintype "passive"))
    )
    (net (code "108") (name "unconnected-(DD6A-X2_OUT-Pad177)") (class "Default")
      (node (ref "DD6") (pin "177") (pinfunction "X2_OUT_177") (pintype "power_in+no_connect"))
    )
    (net (code "109") (name "unconnected-(DD6B-AOUT-Pad46)") (class "Default")
      (node (ref "DD6") (pin "46") (pinfunction "AOUT_46") (pintype "power_in+no_connect"))
    )
    (net (code "110") (name "unconnected-(DD6B-AOUT2-Pad7)") (class "Default")
      (node (ref "DD6") (pin "7") (pinfunction "AOUT2_7") (pintype "power_in+no_connect"))
    )
    (net (code "111") (name "unconnected-(DD6B-BTOUT-Pad181)") (class "Default")
      (node (ref "DD6") (pin "181") (pinfunction "BTOUT_181") (pintype "power_in+no_connect"))
    )
    (net (code "112") (name "unconnected-(DD6B-BTOUT2-Pad80)") (class "Default")
      (node (ref "DD6") (pin "80") (pinfunction "BTOUT2_80") (pintype "power_in+no_connect"))
    )
    (net (code "113") (name "unconnected-(DD6B-CTOUT-Pad180)") (class "Default")
      (node (ref "DD6") (pin "180") (pinfunction "CTOUT_180") (pintype "power_in+no_connect"))
    )
    (net (code "114") (name "unconnected-(DD6B-CTOUT2-Pad81)") (class "Default")
      (node (ref "DD6") (pin "81") (pinfunction "CTOUT2_81") (pintype "power_in+no_connect"))
    )
    (net (code "115") (name "unconnected-(DD6B-DOUT-Pad45)") (class "Default")
      (node (ref "DD6") (pin "45") (pinfunction "DOUT_45") (pintype "power_in+no_connect"))
    )
    (net (code "116") (name "unconnected-(DD6B-DOUT2-Pad8)") (class "Default")
      (node (ref "DD6") (pin "8") (pinfunction "DOUT2_8") (pintype "power_in+no_connect"))
    )
    (net (code "117") (name "unconnected-(DD6B-LED[1][1]-Pad113)") (class "Default")
      (node (ref "DD6") (pin "113") (pinfunction "LED[1][1]_113") (pintype "power_in+no_connect"))
    )
    (net (code "118") (name "unconnected-(DD6B-LED[2][1]-Pad117)") (class "Default")
      (node (ref "DD6") (pin "117") (pinfunction "LED[2][1]_117") (pintype "power_in+no_connect"))
    )
    (net (code "119") (name "unconnected-(DD6B-LED[3][1]-Pad129)") (class "Default")
      (node (ref "DD6") (pin "129") (pinfunction "LED[3][1]_129") (pintype "power_in+no_connect"))
    )
    (net (code "120") (name "unconnected-(DD6B-LED[4][1]-Pad133)") (class "Default")
      (node (ref "DD6") (pin "133") (pinfunction "LED[4][1]_133") (pintype "power_in+no_connect"))
    )
    (net (code "121") (name "unconnected-(DD6B-LED[5][1]-Pad139)") (class "Default")
      (node (ref "DD6") (pin "139") (pinfunction "LED[5][1]_139") (pintype "power_in+no_connect"))
    )
    (net (code "122") (name "unconnected-(DD6B-LED[6][0]-Pad144)") (class "Default")
      (node (ref "DD6") (pin "144") (pinfunction "LED[6][0]_144") (pintype "power_in+no_connect"))
    )
    (net (code "123") (name "unconnected-(DD6B-LED[6][1]-Pad143)") (class "Default")
      (node (ref "DD6") (pin "143") (pinfunction "LED[6][1]_143") (pintype "power_in+no_connect"))
    )
    (net (code "124") (name "unconnected-(DD6B-LED[6][2]-Pad142)") (class "Default")
      (node (ref "DD6") (pin "142") (pinfunction "LED[6][2]_142") (pintype "power_in+no_connect"))
    )
    (net (code "125") (name "unconnected-(DD6B-LED[6][3]-Pad141)") (class "Default")
      (node (ref "DD6") (pin "141") (pinfunction "LED[6][3]_141") (pintype "power_in+no_connect"))
    )
    (net (code "126") (name "unconnected-(DD6B-LED[7][0]-Pad149)") (class "Default")
      (node (ref "DD6") (pin "149") (pinfunction "LED[7][0]_149") (pintype "power_in+no_connect"))
    )
    (net (code "127") (name "unconnected-(DD6B-LED[7][1]-Pad147)") (class "Default")
      (node (ref "DD6") (pin "147") (pinfunction "LED[7][1]_147") (pintype "power_in+no_connect"))
    )
    (net (code "128") (name "unconnected-(DD6B-LED[7][2]-Pad146)") (class "Default")
      (node (ref "DD6") (pin "146") (pinfunction "LED[7][2]_146") (pintype "power_in+no_connect"))
    )
    (net (code "129") (name "unconnected-(DD6B-LED[7][3]-Pad145)") (class "Default")
      (node (ref "DD6") (pin "145") (pinfunction "LED[7][3]_145") (pintype "power_in+no_connect"))
    )
    (net (code "130") (name "unconnected-(DD6B-LED[8][0]-Pad153)") (class "Default")
      (node (ref "DD6") (pin "153") (pinfunction "LED[8][0]_153") (pintype "power_in+no_connect"))
    )
    (net (code "131") (name "unconnected-(DD6B-LED[8][1]-Pad152)") (class "Default")
      (node (ref "DD6") (pin "152") (pinfunction "LED[8][1]_152") (pintype "power_in+no_connect"))
    )
    (net (code "132") (name "unconnected-(DD6B-LED[8][2]-Pad151)") (class "Default")
      (node (ref "DD6") (pin "151") (pinfunction "LED[8][2]_151") (pintype "power_in+no_connect"))
    )
    (net (code "133") (name "unconnected-(DD6B-LED[8][3]-Pad150)") (class "Default")
      (node (ref "DD6") (pin "150") (pinfunction "LED[8][3]_150") (pintype "power_in+no_connect"))
    )
    (net (code "134") (name "unconnected-(DD6B-LED[9][0]-Pad161)") (class "Default")
      (node (ref "DD6") (pin "161") (pinfunction "LED[9][0]_161") (pintype "power_in"))
    )
    (net (code "135") (name "unconnected-(DD6B-LED[9][1]-Pad160)") (class "Default")
      (node (ref "DD6") (pin "160") (pinfunction "LED[9][1]_160") (pintype "power_in+no_connect"))
    )
    (net (code "136") (name "unconnected-(DD6B-LED[9][2]-Pad159)") (class "Default")
      (node (ref "DD6") (pin "159") (pinfunction "LED[9][2]_159") (pintype "power_in+no_connect"))
    )
    (net (code "137") (name "unconnected-(DD6B-LED[9][3]-Pad158)") (class "Default")
      (node (ref "DD6") (pin "158") (pinfunction "LED[9][3]_158") (pintype "power_in+no_connect"))
    )
    (net (code "138") (name "unconnected-(DD6B-MCOL-Pad103)") (class "Default")
      (node (ref "DD6") (pin "103") (pinfunction "MCOL_103") (pintype "power_in+no_connect"))
    )
    (net (code "139") (name "unconnected-(DD6B-MCRS-Pad104)") (class "Default")
      (node (ref "DD6") (pin "104") (pinfunction "MCRS_104") (pintype "power_in+no_connect"))
    )
    (net (code "140") (name "unconnected-(DD6B-MRXC-Pad124)") (class "Default")
      (node (ref "DD6") (pin "124") (pinfunction "MRXC_124") (pintype "power_in+no_connect"))
    )
    (net (code "141") (name "unconnected-(DD6B-MRXDV-Pad119)") (class "Default")
      (node (ref "DD6") (pin "119") (pinfunction "MRXDV_119") (pintype "power_in+no_connect"))
    )
    (net (code "142") (name "unconnected-(DD6B-MRXD[0]-Pad123)") (class "Default")
      (node (ref "DD6") (pin "123") (pinfunction "MRXD[0]_123") (pintype "power_in+no_connect"))
    )
    (net (code "143") (name "unconnected-(DD6B-MRXD[1]-Pad122)") (class "Default")
      (node (ref "DD6") (pin "122") (pinfunction "MRXD[1]_122") (pintype "power_in+no_connect"))
    )
    (net (code "144") (name "unconnected-(DD6B-MRXD[2]-Pad121)") (class "Default")
      (node (ref "DD6") (pin "121") (pinfunction "MRXD[2]_121") (pintype "power_in+no_connect"))
    )
    (net (code "145") (name "unconnected-(DD6B-MRXD[3]-Pad120)") (class "Default")
      (node (ref "DD6") (pin "120") (pinfunction "MRXD[3]_120") (pintype "power_in+no_connect"))
    )
    (net (code "146") (name "unconnected-(DD6B-MTXC-Pad102)") (class "Default")
      (node (ref "DD6") (pin "102") (pinfunction "MTXC_102") (pintype "power_in+no_connect"))
    )
    (net (code "147") (name "unconnected-(DD6B-MTXD[0]-Pad100)") (class "Default")
      (node (ref "DD6") (pin "100") (pinfunction "MTXD[0]_100") (pintype "power_in+no_connect"))
    )
    (net (code "148") (name "unconnected-(DD6B-MTXD[1]-Pad99)") (class "Default")
      (node (ref "DD6") (pin "99") (pinfunction "MTXD[1]_99") (pintype "power_in+no_connect"))
    )
    (net (code "149") (name "unconnected-(DD6B-MTXD[2]-Pad98)") (class "Default")
      (node (ref "DD6") (pin "98") (pinfunction "MTXD[2]_98") (pintype "power_in+no_connect"))
    )
    (net (code "150") (name "unconnected-(DD6B-MTXD[3]-Pad97)") (class "Default")
      (node (ref "DD6") (pin "97") (pinfunction "MTXD[3]_97") (pintype "power_in+no_connect"))
    )
    (net (code "151") (name "unconnected-(DD6B-MTXEN-Pad96)") (class "Default")
      (node (ref "DD6") (pin "96") (pinfunction "MTXEN_96") (pintype "power_in+no_connect"))
    )
    (net (code "152") (name "unconnected-(DD6B-MTXER-Pad101)") (class "Default")
      (node (ref "DD6") (pin "101") (pinfunction "MTXER_101") (pintype "power_in+no_connect"))
    )
    (net (code "153") (name "unconnected-(DD6B-MUX[1]-Pad83)") (class "Default")
      (node (ref "DD6") (pin "83") (pinfunction "MUX[1]_83") (pintype "power_in+no_connect"))
    )
    (net (code "154") (name "unconnected-(DD6B-MUX[2]-Pad84)") (class "Default")
      (node (ref "DD6") (pin "84") (pinfunction "MUX[2]_84") (pintype "power_in+no_connect"))
    )
    (net (code "155") (name "unconnected-(DD6B-QH[2]-Pad14)") (class "Default")
      (node (ref "DD6") (pin "14") (pinfunction "QH[2]_14") (pintype "power_in+no_connect"))
    )
    (net (code "156") (name "unconnected-(DD6B-QH[3]-Pad13)") (class "Default")
      (node (ref "DD6") (pin "13") (pinfunction "QH[3]_13") (pintype "power_in+no_connect"))
    )
    (net (code "157") (name "unconnected-(DD6B-QH[4]-Pad12)") (class "Default")
      (node (ref "DD6") (pin "12") (pinfunction "QH[4]_12") (pintype "power_in+no_connect"))
    )
    (net (code "158") (name "unconnected-(DD6B-QH[5]-Pad11)") (class "Default")
      (node (ref "DD6") (pin "11") (pinfunction "QH[5]_11") (pintype "power_in+no_connect"))
    )
    (net (code "159") (name "unconnected-(DD6B-QL[2]-Pad39)") (class "Default")
      (node (ref "DD6") (pin "39") (pinfunction "QL[2]_39") (pintype "power_in+no_connect"))
    )
    (net (code "160") (name "unconnected-(DD6B-QL[3]-Pad40)") (class "Default")
      (node (ref "DD6") (pin "40") (pinfunction "QL[3]_40") (pintype "power_in+no_connect"))
    )
    (net (code "161") (name "unconnected-(DD6B-QL[4]-Pad41)") (class "Default")
      (node (ref "DD6") (pin "41") (pinfunction "QL[4]_41") (pintype "power_in+no_connect"))
    )
    (net (code "162") (name "unconnected-(DD6B-QL[5]-Pad42)") (class "Default")
      (node (ref "DD6") (pin "42") (pinfunction "QL[5]_42") (pintype "power_in+no_connect"))
    )
    (net (code "163") (name "unconnected-(DD6B-Reserve-Pad174)") (class "Default")
      (node (ref "DD6") (pin "174") (pinfunction "Reserve_174") (pintype "power_in+no_connect"))
    )
    (net (code "164") (name "unconnected-(DD6B-Reserve-Pad175)") (class "Default")
      (node (ref "DD6") (pin "175") (pinfunction "Reserve_175") (pintype "power_in+no_connect"))
    )
    (net (code "165") (name "unconnected-(DD6B-TEST[1]-Pad85)") (class "Default")
      (node (ref "DD6") (pin "85") (pinfunction "TEST[1]_85") (pintype "power_in+no_connect"))
    )
    (net (code "166") (name "unconnected-(DD6B-TEST[2]-Pad86)") (class "Default")
      (node (ref "DD6") (pin "86") (pinfunction "TEST[2]_86") (pintype "power_in+no_connect"))
    )
    (net (code "167") (name "unconnected-(DD6B-T[1]-Pad88)") (class "Default")
      (node (ref "DD6") (pin "88") (pinfunction "T[1]_88") (pintype "power_in+no_connect"))
    )
    (net (code "168") (name "unconnected-(DD6B-T[2]-Pad89)") (class "Default")
      (node (ref "DD6") (pin "89") (pinfunction "T[2]_89") (pintype "power_in+no_connect"))
    )
    (net (code "169") (name "unconnected-(DD6B-T[3]-Pad90)") (class "Default")
      (node (ref "DD6") (pin "90") (pinfunction "T[3]_90") (pintype "power_in+no_connect"))
    )
    (net (code "170") (name "unconnected-(DD6B-T[5]-Pad172)") (class "Default")
      (node (ref "DD6") (pin "172") (pinfunction "T[5]_172") (pintype "power_in+no_connect"))
    )
    (net (code "171") (name "unconnected-(DD6C-RXM[6]-Pad48)") (class "Default")
      (node (ref "DD6") (pin "48") (pinfunction "RXM[6]_48") (pintype "power_in+no_connect"))
    )
    (net (code "172") (name "unconnected-(DD6C-RXM[7]-Pad55)") (class "Default")
      (node (ref "DD6") (pin "55") (pinfunction "RXM[7]_55") (pintype "power_in+no_connect"))
    )
    (net (code "173") (name "unconnected-(DD6C-RXM[8]-Pad65)") (class "Default")
      (node (ref "DD6") (pin "65") (pinfunction "RXM[8]_65") (pintype "power_in+no_connect"))
    )
    (net (code "174") (name "unconnected-(DD6C-RXP[6]-Pad47)") (class "Default")
      (node (ref "DD6") (pin "47") (pinfunction "RXP[6]_47") (pintype "power_in+no_connect"))
    )
    (net (code "175") (name "unconnected-(DD6C-RXP[7]-Pad54)") (class "Default")
      (node (ref "DD6") (pin "54") (pinfunction "RXP[7]_54") (pintype "power_in+no_connect"))
    )
    (net (code "176") (name "unconnected-(DD6C-RXP[8]-Pad64)") (class "Default")
      (node (ref "DD6") (pin "64") (pinfunction "RXP[8]_64") (pintype "power_in+no_connect"))
    )
    (net (code "177") (name "unconnected-(DD6C-TXM[6]-Pad44)") (class "Default")
      (node (ref "DD6") (pin "44") (pinfunction "TXM[6]_44") (pintype "power_in+no_connect"))
    )
    (net (code "178") (name "unconnected-(DD6C-TXM[7]-Pad58)") (class "Default")
      (node (ref "DD6") (pin "58") (pinfunction "TXM[7]_58") (pintype "power_in+no_connect"))
    )
    (net (code "179") (name "unconnected-(DD6C-TXM[8]-Pad62)") (class "Default")
      (node (ref "DD6") (pin "62") (pinfunction "TXM[8]_62") (pintype "power_in+no_connect"))
    )
    (net (code "180") (name "unconnected-(DD6C-TXP[6]-Pad43)") (class "Default")
      (node (ref "DD6") (pin "43") (pinfunction "TXP[6]_43") (pintype "power_in+no_connect"))
    )
    (net (code "181") (name "unconnected-(DD6C-TXP[7]-Pad57)") (class "Default")
      (node (ref "DD6") (pin "57") (pinfunction "TXP[7]_57") (pintype "power_in+no_connect"))
    )
    (net (code "182") (name "unconnected-(DD6C-TXP[8]-Pad61)") (class "Default")
      (node (ref "DD6") (pin "61") (pinfunction "TXP[8]_61") (pintype "power_in+no_connect"))
    )
    (net (code "183") (name "unconnected-(G2-NC-Pad1)") (class "Default")
      (node (ref "G2") (pin "1") (pinfunction "NC_1") (pintype "power_in+no_connect"))
    )
  )
)
